# PT_2016_PB_MAIN_Rev1.net
KiCad netlist of a schematic drawn in EAGLE
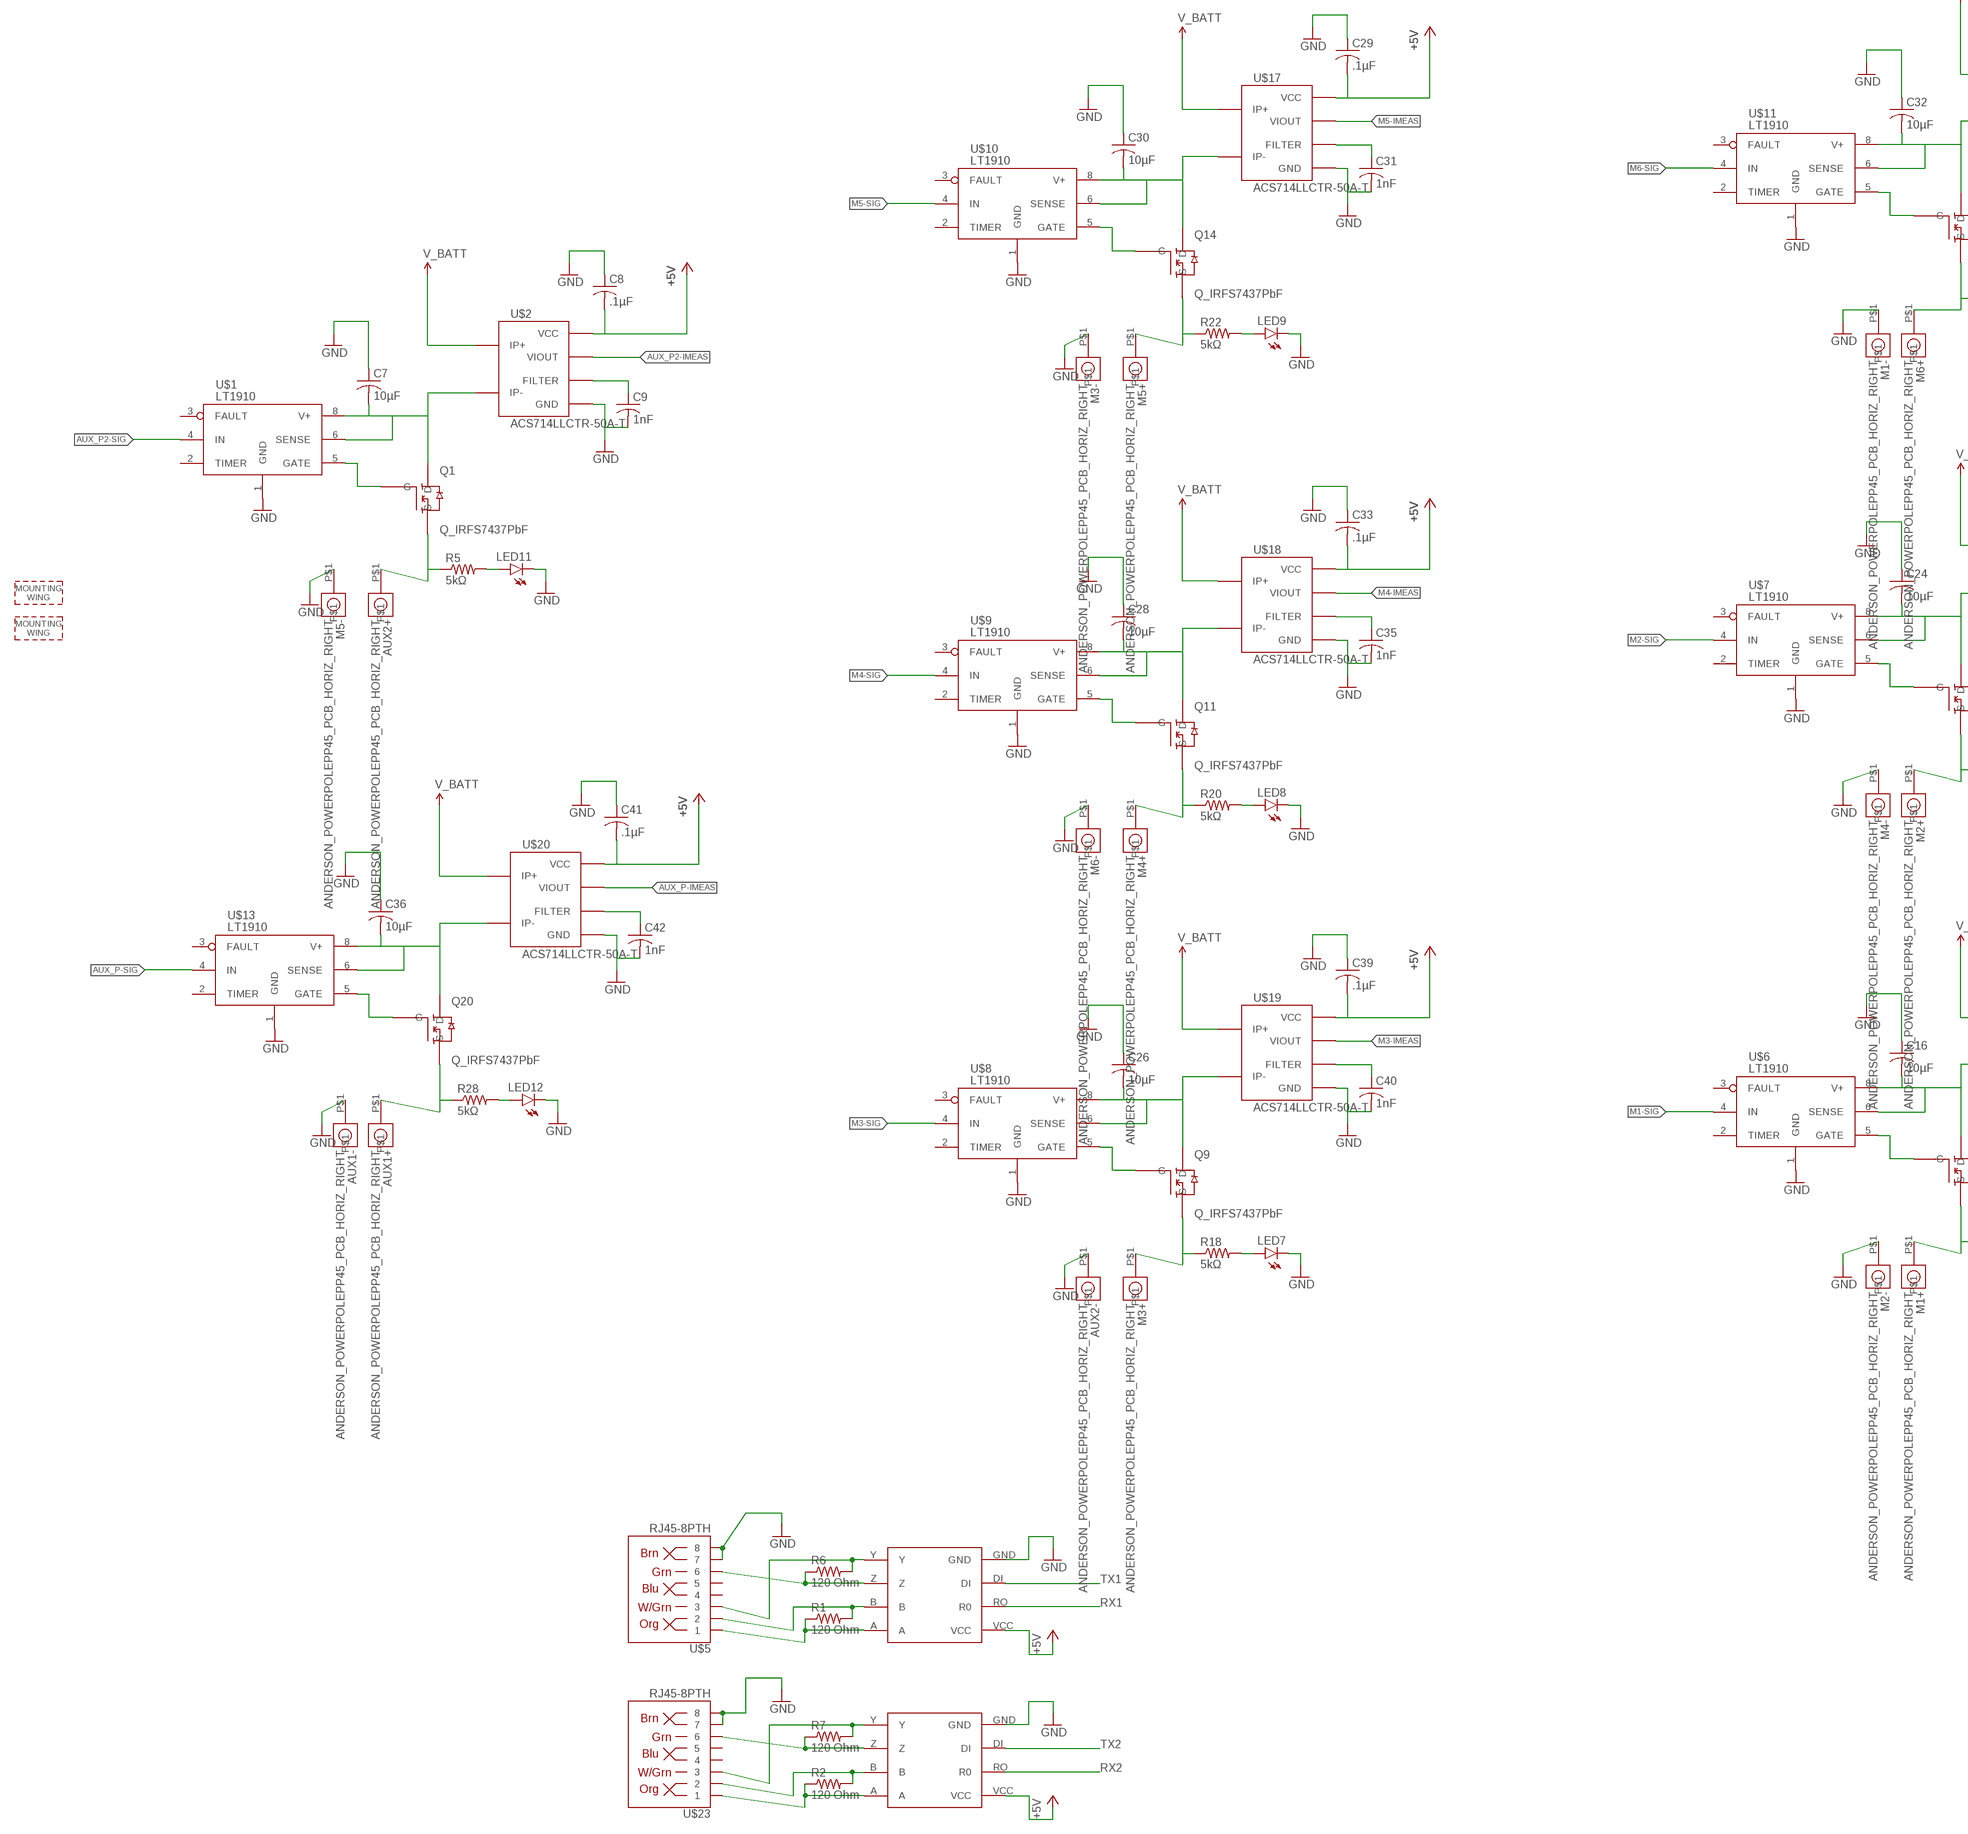
[diagram p0: schematic, sheet 1, part 1 of 2]
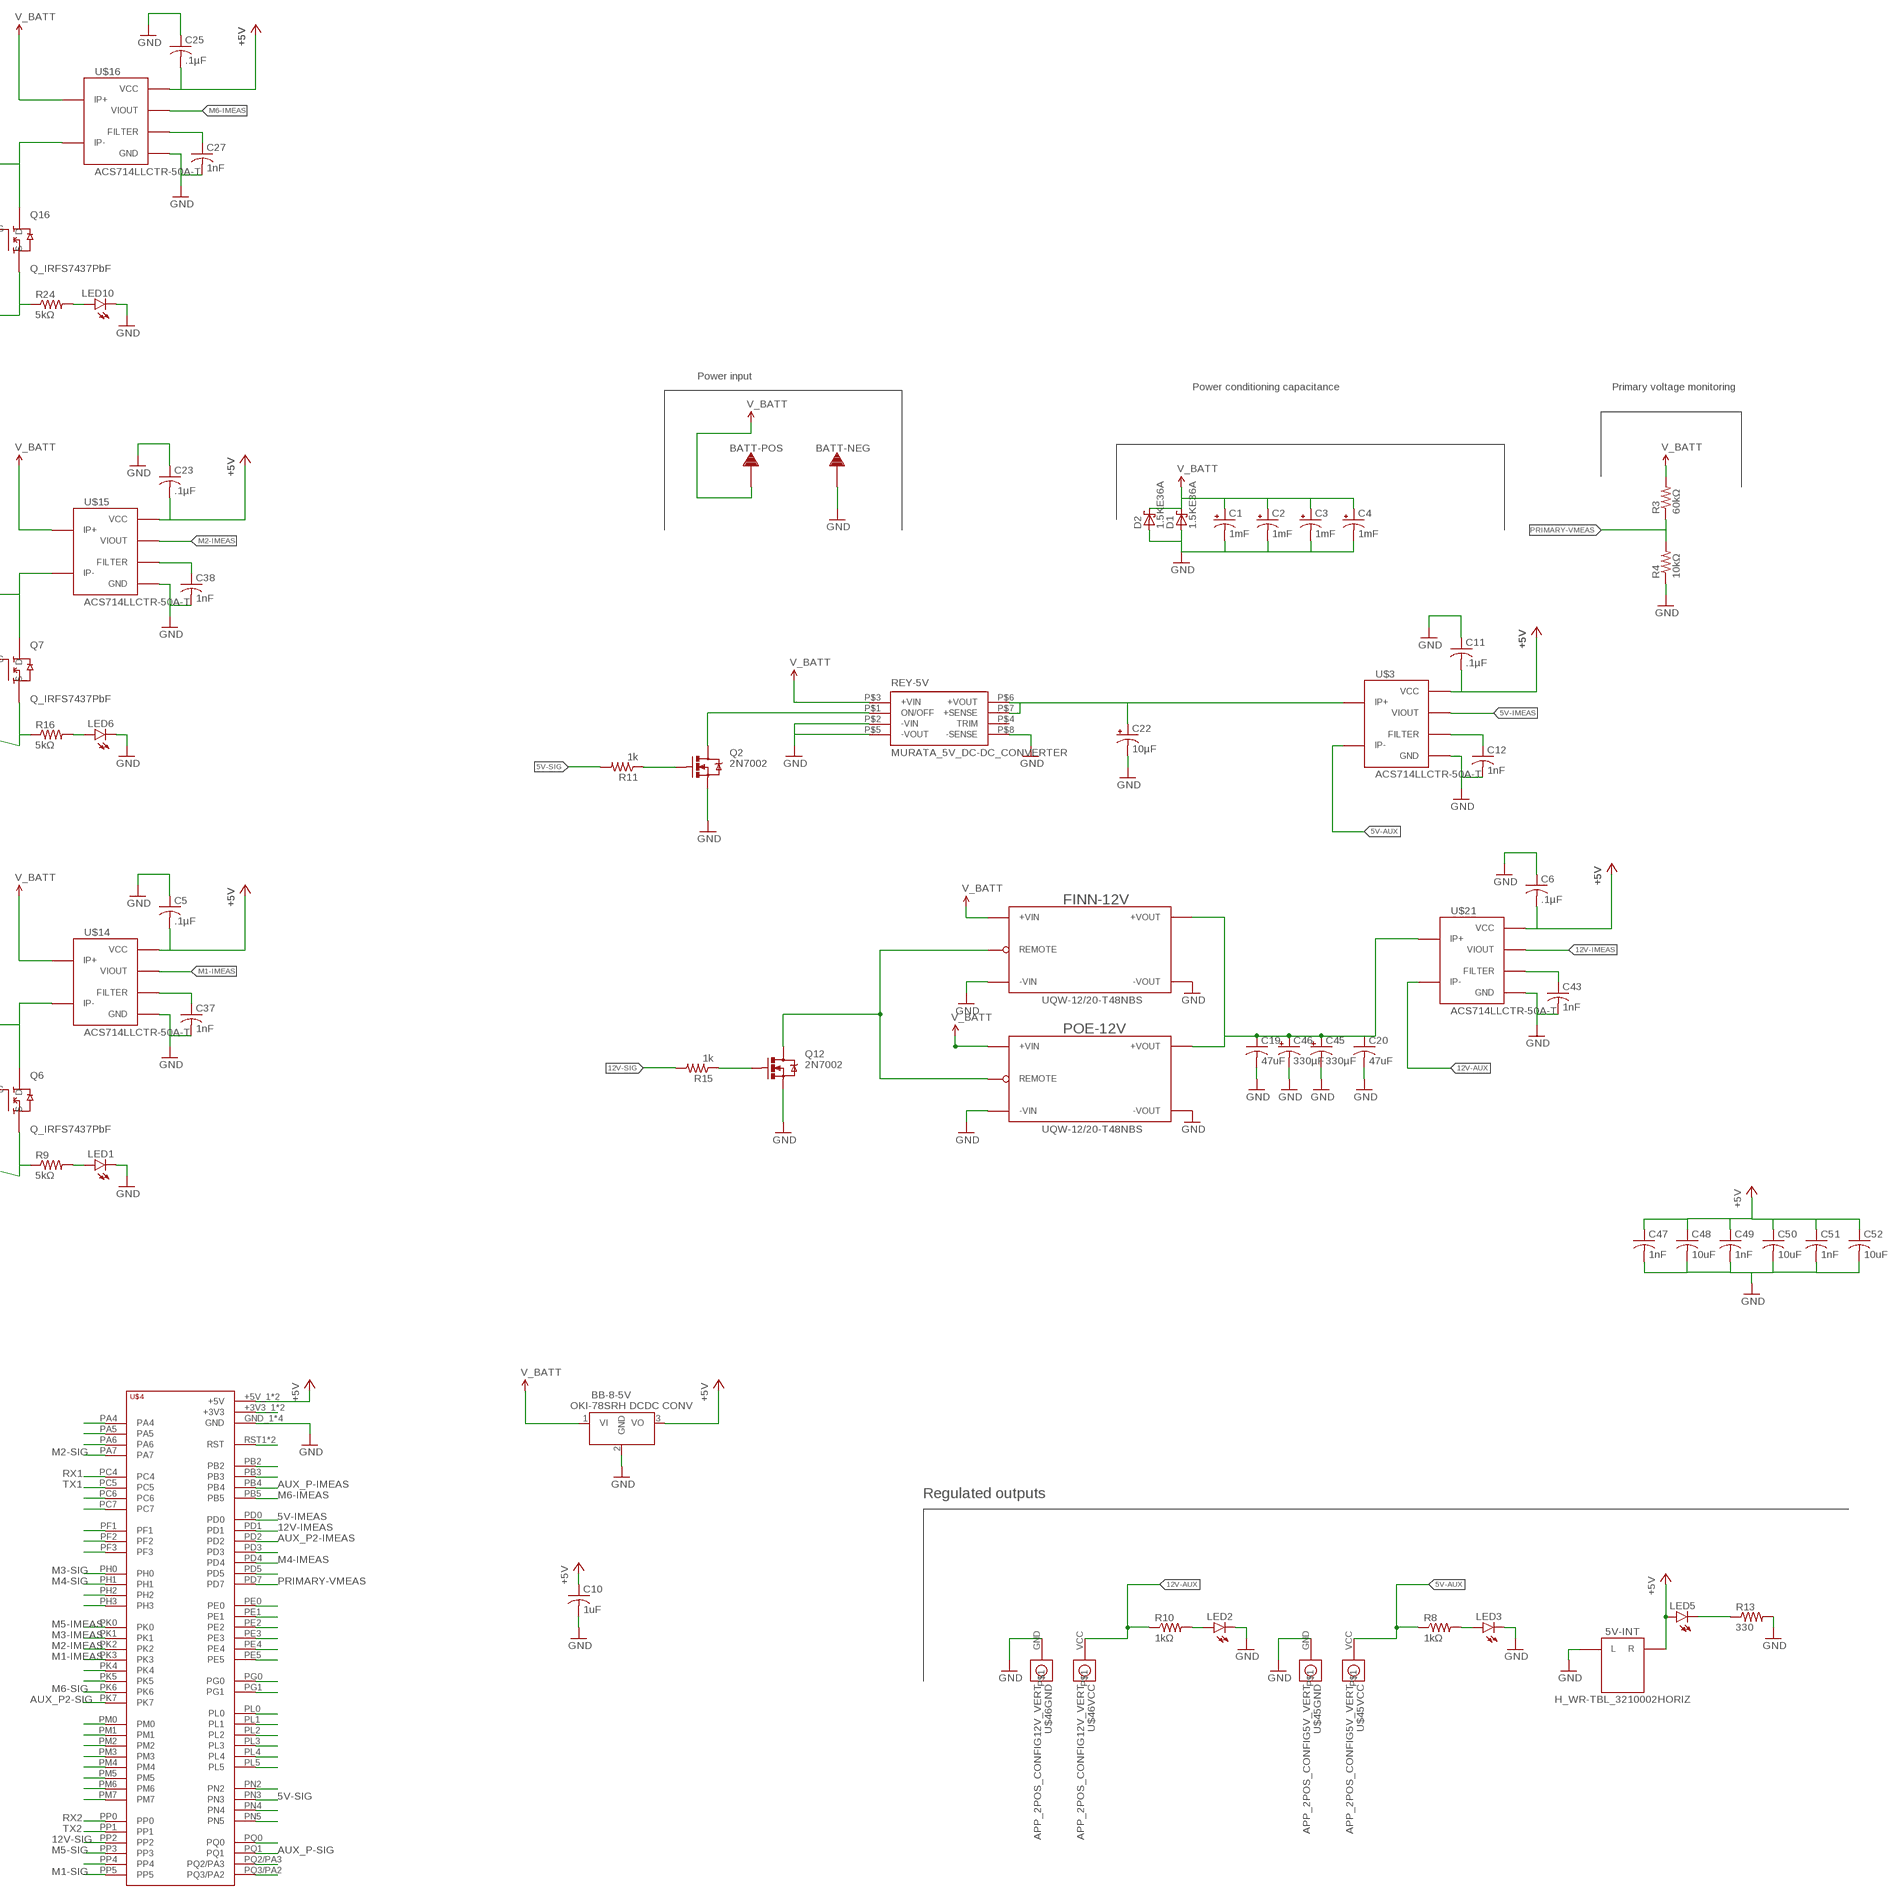
[diagram p1: schematic, sheet 1, part 2 of 2]

(export (version "E")
  (design (tool "Eeschema 10.0.6"))
  (components
    (comp (ref "5V-INT")
      (value "H_WR-TBL_3210002HORIZ")
      (footprint "eagle-import:691322110002")
      (libsource (lib "eagle-import") (part "H_WR-TBL_3210002HORIZ"))
    )
    (comp (ref "AUX1+")
      (value "ANDERSON_POWERPOLEPP45_PCB_HORIZ_RIGHT")
      (footprint "eagle-import:APP45_PCB_HORIZ_RIGHT")
      (libsource (lib "eagle-import") (part "ANDERSON_POWERPOLEPP45_PCB_HORIZ_RIGHT"))
    )
    (comp (ref "AUX1-")
      (value "ANDERSON_POWERPOLEPP45_PCB_HORIZ_RIGHT")
      (footprint "eagle-import:APP45_PCB_HORIZ_RIGHT")
      (libsource (lib "eagle-import") (part "ANDERSON_POWERPOLEPP45_PCB_HORIZ_RIGHT"))
    )
    (comp (ref "AUX2+")
      (value "ANDERSON_POWERPOLEPP45_PCB_HORIZ_RIGHT")
      (footprint "eagle-import:APP45_PCB_HORIZ_RIGHT")
      (libsource (lib "eagle-import") (part "ANDERSON_POWERPOLEPP45_PCB_HORIZ_RIGHT"))
    )
    (comp (ref "AUX2-")
      (value "ANDERSON_POWERPOLEPP45_PCB_HORIZ_RIGHT")
      (footprint "eagle-import:APP45_PCB_HORIZ_RIGHT")
      (libsource (lib "eagle-import") (part "ANDERSON_POWERPOLEPP45_PCB_HORIZ_RIGHT"))
    )
    (comp (ref "BATT-NEG")
      (value "TERMINAL_HOLE")
      (footprint "eagle-import:LARGE_TERMINAL_HOLE")
      (libsource (lib "eagle-import") (part "TERMINAL_HOLE"))
    )
    (comp (ref "BATT-POS")
      (value "TERMINAL_HOLE")
      (footprint "eagle-import:LARGE_TERMINAL_HOLE")
      (libsource (lib "eagle-import") (part "TERMINAL_HOLE"))
    )
    (comp (ref "BB-8-5V")
      (value "Q_OKI-78SR")
      (footprint "eagle-import:OKI-78SRH")
      (libsource (lib "eagle-import") (part "Q_OKI-78SR"))
    )
    (comp (ref "C1")
      (value "1mF")
      (footprint "eagle-import:C_12.5MM")
      (libsource (lib "eagle-import") (part "C_POL12.5MM_NORMAL"))
    )
    (comp (ref "C2")
      (value "1mF")
      (footprint "eagle-import:C_12.5MM")
      (libsource (lib "eagle-import") (part "C_POL12.5MM_NORMAL"))
    )
    (comp (ref "C3")
      (value "1mF")
      (footprint "eagle-import:C_12.5MM")
      (libsource (lib "eagle-import") (part "C_POL12.5MM_NORMAL"))
    )
    (comp (ref "C4")
      (value "1mF")
      (footprint "eagle-import:C_12.5MM")
      (libsource (lib "eagle-import") (part "C_POL12.5MM_NORMAL"))
    )
    (comp (ref "C5")
      (value ".1µF")
      (footprint "eagle-import:C1206")
      (libsource (lib "eagle-import") (part "C-USC1206"))
    )
    (comp (ref "C6")
      (value ".1µF")
      (footprint "eagle-import:C1206")
      (libsource (lib "eagle-import") (part "C-USC1206"))
    )
    (comp (ref "C7")
      (value "10µF")
      (footprint "eagle-import:C1206")
      (libsource (lib "eagle-import") (part "C-USC1206"))
    )
    (comp (ref "C8")
      (value ".1µF")
      (footprint "eagle-import:C1206")
      (libsource (lib "eagle-import") (part "C-USC1206"))
    )
    (comp (ref "C9")
      (value "1nF")
      (footprint "eagle-import:C1206")
      (libsource (lib "eagle-import") (part "C-USC1206"))
    )
    (comp (ref "C10")
      (value "1uF")
      (footprint "eagle-import:C1206")
      (libsource (lib "eagle-import") (part "C-USC1206"))
    )
    (comp (ref "C11")
      (value ".1µF")
      (footprint "eagle-import:C1206")
      (libsource (lib "eagle-import") (part "C-USC1206"))
    )
    (comp (ref "C12")
      (value "1nF")
      (footprint "eagle-import:C1206")
      (libsource (lib "eagle-import") (part "C-USC1206"))
    )
    (comp (ref "C16")
      (value "10µF")
      (footprint "eagle-import:C1206")
      (libsource (lib "eagle-import") (part "C-USC1206"))
    )
    (comp (ref "C19")
      (value "47uF")
      (footprint "eagle-import:C1206")
      (libsource (lib "eagle-import") (part "C-USC1206"))
    )
    (comp (ref "C20")
      (value "47uF")
      (footprint "eagle-import:C1206")
      (libsource (lib "eagle-import") (part "C-USC1206"))
    )
    (comp (ref "C22")
      (value "10µF")
      (footprint "eagle-import:E5-8,5")
      (libsource (lib "eagle-import") (part "CPOL-USE5-8.5"))
    )
    (comp (ref "C23")
      (value ".1µF")
      (footprint "eagle-import:C1206")
      (libsource (lib "eagle-import") (part "C-USC1206"))
    )
    (comp (ref "C24")
      (value "10µF")
      (footprint "eagle-import:C1206")
      (libsource (lib "eagle-import") (part "C-USC1206"))
    )
    (comp (ref "C25")
      (value ".1µF")
      (footprint "eagle-import:C1206")
      (libsource (lib "eagle-import") (part "C-USC1206"))
    )
    (comp (ref "C26")
      (value "10µF")
      (footprint "eagle-import:C1206")
      (libsource (lib "eagle-import") (part "C-USC1206"))
    )
    (comp (ref "C27")
      (value "1nF")
      (footprint "eagle-import:C1206")
      (libsource (lib "eagle-import") (part "C-USC1206"))
    )
    (comp (ref "C28")
      (value "10µF")
      (footprint "eagle-import:C1206")
      (libsource (lib "eagle-import") (part "C-USC1206"))
    )
    (comp (ref "C29")
      (value ".1µF")
      (footprint "eagle-import:C1206")
      (libsource (lib "eagle-import") (part "C-USC1206"))
    )
    (comp (ref "C30")
      (value "10µF")
      (footprint "eagle-import:C1206")
      (libsource (lib "eagle-import") (part "C-USC1206"))
    )
    (comp (ref "C31")
      (value "1nF")
      (footprint "eagle-import:C1206")
      (libsource (lib "eagle-import") (part "C-USC1206"))
    )
    (comp (ref "C32")
      (value "10µF")
      (footprint "eagle-import:C1206")
      (libsource (lib "eagle-import") (part "C-USC1206"))
    )
    (comp (ref "C33")
      (value ".1µF")
      (footprint "eagle-import:C1206")
      (libsource (lib "eagle-import") (part "C-USC1206"))
    )
    (comp (ref "C35")
      (value "1nF")
      (footprint "eagle-import:C1206")
      (libsource (lib "eagle-import") (part "C-USC1206"))
    )
    (comp (ref "C36")
      (value "10µF")
      (footprint "eagle-import:C1206")
      (libsource (lib "eagle-import") (part "C-USC1206"))
    )
    (comp (ref "C37")
      (value "1nF")
      (footprint "eagle-import:C1206")
      (libsource (lib "eagle-import") (part "C-USC1206"))
    )
    (comp (ref "C38")
      (value "1nF")
      (footprint "eagle-import:C1206")
      (libsource (lib "eagle-import") (part "C-USC1206"))
    )
    (comp (ref "C39")
      (value ".1µF")
      (footprint "eagle-import:C1206")
      (libsource (lib "eagle-import") (part "C-USC1206"))
    )
    (comp (ref "C40")
      (value "1nF")
      (footprint "eagle-import:C1206")
      (libsource (lib "eagle-import") (part "C-USC1206"))
    )
    (comp (ref "C41")
      (value ".1µF")
      (footprint "eagle-import:C1206")
      (libsource (lib "eagle-import") (part "C-USC1206"))
    )
    (comp (ref "C42")
      (value "1nF")
      (footprint "eagle-import:C1206")
      (libsource (lib "eagle-import") (part "C-USC1206"))
    )
    (comp (ref "C43")
      (value "1nF")
      (footprint "eagle-import:C1206")
      (libsource (lib "eagle-import") (part "C-USC1206"))
    )
    (comp (ref "C45")
      (value "330µF")
      (footprint "eagle-import:E5-8,5")
      (libsource (lib "eagle-import") (part "CPOL-USE5-8.5"))
    )
    (comp (ref "C46")
      (value "330µF")
      (footprint "eagle-import:E5-8,5")
      (libsource (lib "eagle-import") (part "CPOL-USE5-8.5"))
    )
    (comp (ref "C47")
      (value "1nF")
      (footprint "eagle-import:C1206")
      (libsource (lib "eagle-import") (part "C-USC1206"))
    )
    (comp (ref "C48")
      (value "10uF")
      (footprint "eagle-import:C1206")
      (libsource (lib "eagle-import") (part "C-USC1206"))
    )
    (comp (ref "C49")
      (value "1nF")
      (footprint "eagle-import:C1206")
      (libsource (lib "eagle-import") (part "C-USC1206"))
    )
    (comp (ref "C50")
      (value "10uF")
      (footprint "eagle-import:C1206")
      (libsource (lib "eagle-import") (part "C-USC1206"))
    )
    (comp (ref "C51")
      (value "1nF")
      (footprint "eagle-import:C1206")
      (libsource (lib "eagle-import") (part "C-USC1206"))
    )
    (comp (ref "C52")
      (value "10uF")
      (footprint "eagle-import:C1206")
      (libsource (lib "eagle-import") (part "C-USC1206"))
    )
    (comp (ref "D1")
      (value "1.5KE36A")
      (footprint "eagle-import:CB429-17")
      (libsource (lib "eagle-import") (part "15KEXX"))
    )
    (comp (ref "D2")
      (value "1.5KE36A")
      (footprint "eagle-import:CB429-17")
      (libsource (lib "eagle-import") (part "15KEXX"))
    )
    (comp (ref "FINN-12V")
      (value "UQW-12/20-T48NBS")
      (footprint "eagle-import:U-T48-QB-NO_TRIM")
      (libsource (lib "eagle-import") (part "UQW-12/20-T48NBS"))
    )
    (comp (ref "LED1")
      (value "LED1206")
      (footprint "eagle-import:LED-1206")
      (libsource (lib "eagle-import") (part "LED1206"))
    )
    (comp (ref "LED2")
      (value "LED1206")
      (footprint "eagle-import:LED-1206")
      (libsource (lib "eagle-import") (part "LED1206"))
    )
    (comp (ref "LED3")
      (value "LED1206")
      (footprint "eagle-import:LED-1206")
      (libsource (lib "eagle-import") (part "LED1206"))
    )
    (comp (ref "LED5")
      (value "LED1206")
      (footprint "eagle-import:LED-1206")
      (libsource (lib "eagle-import") (part "LED1206"))
    )
    (comp (ref "LED6")
      (value "LED1206")
      (footprint "eagle-import:LED-1206")
      (libsource (lib "eagle-import") (part "LED1206"))
    )
    (comp (ref "LED7")
      (value "LED1206")
      (footprint "eagle-import:LED-1206")
      (libsource (lib "eagle-import") (part "LED1206"))
    )
    (comp (ref "LED8")
      (value "LED1206")
      (footprint "eagle-import:LED-1206")
      (libsource (lib "eagle-import") (part "LED1206"))
    )
    (comp (ref "LED9")
      (value "LED1206")
      (footprint "eagle-import:LED-1206")
      (libsource (lib "eagle-import") (part "LED1206"))
    )
    (comp (ref "LED10")
      (value "LED1206")
      (footprint "eagle-import:LED-1206")
      (libsource (lib "eagle-import") (part "LED1206"))
    )
    (comp (ref "LED11")
      (value "LED1206")
      (footprint "eagle-import:LED-1206")
      (libsource (lib "eagle-import") (part "LED1206"))
    )
    (comp (ref "LED12")
      (value "LED1206")
      (footprint "eagle-import:LED-1206")
      (libsource (lib "eagle-import") (part "LED1206"))
    )
    (comp (ref "M1+")
      (value "ANDERSON_POWERPOLEPP45_PCB_HORIZ_RIGHT")
      (footprint "eagle-import:APP45_PCB_HORIZ_RIGHT")
      (libsource (lib "eagle-import") (part "ANDERSON_POWERPOLEPP45_PCB_HORIZ_RIGHT"))
    )
    (comp (ref "M1-")
      (value "ANDERSON_POWERPOLEPP45_PCB_HORIZ_RIGHT")
      (footprint "eagle-import:APP45_PCB_HORIZ_RIGHT")
      (libsource (lib "eagle-import") (part "ANDERSON_POWERPOLEPP45_PCB_HORIZ_RIGHT"))
    )
    (comp (ref "M2+")
      (value "ANDERSON_POWERPOLEPP45_PCB_HORIZ_RIGHT")
      (footprint "eagle-import:APP45_PCB_HORIZ_RIGHT")
      (libsource (lib "eagle-import") (part "ANDERSON_POWERPOLEPP45_PCB_HORIZ_RIGHT"))
    )
    (comp (ref "M2-")
      (value "ANDERSON_POWERPOLEPP45_PCB_HORIZ_RIGHT")
      (footprint "eagle-import:APP45_PCB_HORIZ_RIGHT")
      (libsource (lib "eagle-import") (part "ANDERSON_POWERPOLEPP45_PCB_HORIZ_RIGHT"))
    )
    (comp (ref "M3+")
      (value "ANDERSON_POWERPOLEPP45_PCB_HORIZ_RIGHT")
      (footprint "eagle-import:APP45_PCB_HORIZ_RIGHT")
      (libsource (lib "eagle-import") (part "ANDERSON_POWERPOLEPP45_PCB_HORIZ_RIGHT"))
    )
    (comp (ref "M3-")
      (value "ANDERSON_POWERPOLEPP45_PCB_HORIZ_RIGHT")
      (footprint "eagle-import:APP45_PCB_HORIZ_RIGHT")
      (libsource (lib "eagle-import") (part "ANDERSON_POWERPOLEPP45_PCB_HORIZ_RIGHT"))
    )
    (comp (ref "M4+")
      (value "ANDERSON_POWERPOLEPP45_PCB_HORIZ_RIGHT")
      (footprint "eagle-import:APP45_PCB_HORIZ_RIGHT")
      (libsource (lib "eagle-import") (part "ANDERSON_POWERPOLEPP45_PCB_HORIZ_RIGHT"))
    )
    (comp (ref "M4-")
      (value "ANDERSON_POWERPOLEPP45_PCB_HORIZ_RIGHT")
      (footprint "eagle-import:APP45_PCB_HORIZ_RIGHT")
      (libsource (lib "eagle-import") (part "ANDERSON_POWERPOLEPP45_PCB_HORIZ_RIGHT"))
    )
    (comp (ref "M5+")
      (value "ANDERSON_POWERPOLEPP45_PCB_HORIZ_RIGHT")
      (footprint "eagle-import:APP45_PCB_HORIZ_RIGHT")
      (libsource (lib "eagle-import") (part "ANDERSON_POWERPOLEPP45_PCB_HORIZ_RIGHT"))
    )
    (comp (ref "M5-")
      (value "ANDERSON_POWERPOLEPP45_PCB_HORIZ_RIGHT")
      (footprint "eagle-import:APP45_PCB_HORIZ_RIGHT")
      (libsource (lib "eagle-import") (part "ANDERSON_POWERPOLEPP45_PCB_HORIZ_RIGHT"))
    )
    (comp (ref "M6+")
      (value "ANDERSON_POWERPOLEPP45_PCB_HORIZ_RIGHT")
      (footprint "eagle-import:APP45_PCB_HORIZ_RIGHT")
      (libsource (lib "eagle-import") (part "ANDERSON_POWERPOLEPP45_PCB_HORIZ_RIGHT"))
    )
    (comp (ref "M6-")
      (value "ANDERSON_POWERPOLEPP45_PCB_HORIZ_RIGHT")
      (footprint "eagle-import:APP45_PCB_HORIZ_RIGHT")
      (libsource (lib "eagle-import") (part "ANDERSON_POWERPOLEPP45_PCB_HORIZ_RIGHT"))
    )
    (comp (ref "POE-12V")
      (value "UQW-12/20-T48NBS")
      (footprint "eagle-import:U-T48-QB-NO_TRIM")
      (libsource (lib "eagle-import") (part "UQW-12/20-T48NBS"))
    )
    (comp (ref "Q1")
      (value "Q_IRFS7437PbF")
      (footprint "eagle-import:D2PACK")
      (libsource (lib "eagle-import") (part "Q_IRF7437SMD"))
    )
    (comp (ref "Q2")
      (value "2N7002")
      (footprint "eagle-import:SOT323")
      (libsource (lib "eagle-import") (part "MOSFET-NCHANNEL2N7002PW"))
    )
    (comp (ref "Q6")
      (value "Q_IRFS7437PbF")
      (footprint "eagle-import:D2PACK")
      (libsource (lib "eagle-import") (part "Q_IRF7437SMD"))
    )
    (comp (ref "Q7")
      (value "Q_IRFS7437PbF")
      (footprint "eagle-import:D2PACK")
      (libsource (lib "eagle-import") (part "Q_IRF7437SMD"))
    )
    (comp (ref "Q9")
      (value "Q_IRFS7437PbF")
      (footprint "eagle-import:D2PACK")
      (libsource (lib "eagle-import") (part "Q_IRF7437SMD"))
    )
    (comp (ref "Q11")
      (value "Q_IRFS7437PbF")
      (footprint "eagle-import:D2PACK")
      (libsource (lib "eagle-import") (part "Q_IRF7437SMD"))
    )
    (comp (ref "Q12")
      (value "2N7002")
      (footprint "eagle-import:SOT323")
      (libsource (lib "eagle-import") (part "MOSFET-NCHANNEL2N7002PW"))
    )
    (comp (ref "Q14")
      (value "Q_IRFS7437PbF")
      (footprint "eagle-import:D2PACK")
      (libsource (lib "eagle-import") (part "Q_IRF7437SMD"))
    )
    (comp (ref "Q16")
      (value "Q_IRFS7437PbF")
      (footprint "eagle-import:D2PACK")
      (libsource (lib "eagle-import") (part "Q_IRF7437SMD"))
    )
    (comp (ref "Q20")
      (value "Q_IRFS7437PbF")
      (footprint "eagle-import:D2PACK")
      (libsource (lib "eagle-import") (part "Q_IRF7437SMD"))
    )
    (comp (ref "R1")
      (value "120 Ohm")
      (footprint "eagle-import:1206")
      (libsource (lib "eagle-import") (part "RESISTOR1206"))
    )
    (comp (ref "R2")
      (value "120 Ohm")
      (footprint "eagle-import:1206")
      (libsource (lib "eagle-import") (part "RESISTOR1206"))
    )
    (comp (ref "R3")
      (value "60kΩ")
      (footprint "eagle-import:R1206")
      (libsource (lib "eagle-import") (part "R-US_R1206"))
    )
    (comp (ref "R4")
      (value "10kΩ")
      (footprint "eagle-import:R1206")
      (libsource (lib "eagle-import") (part "R-US_R1206"))
    )
    (comp (ref "R5")
      (value "5kΩ")
      (footprint "eagle-import:1206")
      (libsource (lib "eagle-import") (part "RESISTOR1206"))
    )
    (comp (ref "R6")
      (value "120 Ohm")
      (footprint "eagle-import:1206")
      (libsource (lib "eagle-import") (part "RESISTOR1206"))
    )
    (comp (ref "R7")
      (value "120 Ohm")
      (footprint "eagle-import:1206")
      (libsource (lib "eagle-import") (part "RESISTOR1206"))
    )
    (comp (ref "R8")
      (value "1kΩ")
      (footprint "eagle-import:1206")
      (libsource (lib "eagle-import") (part "RESISTOR1206"))
    )
    (comp (ref "R9")
      (value "5kΩ")
      (footprint "eagle-import:1206")
      (libsource (lib "eagle-import") (part "RESISTOR1206"))
    )
    (comp (ref "R10")
      (value "1kΩ")
      (footprint "eagle-import:1206")
      (libsource (lib "eagle-import") (part "RESISTOR1206"))
    )
    (comp (ref "R11")
      (value "1k")
      (footprint "eagle-import:R1206")
      (libsource (lib "eagle-import") (part "R-US_R1206"))
    )
    (comp (ref "R13")
      (value "330")
      (footprint "eagle-import:1206")
      (libsource (lib "eagle-import") (part "RESISTOR1206"))
    )
    (comp (ref "R15")
      (value "1k")
      (footprint "eagle-import:R1206")
      (libsource (lib "eagle-import") (part "R-US_R1206"))
    )
    (comp (ref "R16")
      (value "5kΩ")
      (footprint "eagle-import:1206")
      (libsource (lib "eagle-import") (part "RESISTOR1206"))
    )
    (comp (ref "R18")
      (value "5kΩ")
      (footprint "eagle-import:1206")
      (libsource (lib "eagle-import") (part "RESISTOR1206"))
    )
    (comp (ref "R20")
      (value "5kΩ")
      (footprint "eagle-import:1206")
      (libsource (lib "eagle-import") (part "RESISTOR1206"))
    )
    (comp (ref "R22")
      (value "5kΩ")
      (footprint "eagle-import:1206")
      (libsource (lib "eagle-import") (part "RESISTOR1206"))
    )
    (comp (ref "R24")
      (value "5kΩ")
      (footprint "eagle-import:1206")
      (libsource (lib "eagle-import") (part "RESISTOR1206"))
    )
    (comp (ref "R28")
      (value "5kΩ")
      (footprint "eagle-import:1206")
      (libsource (lib "eagle-import") (part "RESISTOR1206"))
    )
    (comp (ref "REY-5V")
      (value "MURATA_5V_DC-DC_CONVERTER")
      (footprint "eagle-import:MURATA_5V_DC-DC_CONVERTER")
      (libsource (lib "eagle-import") (part "MURATA_5V_DC-DC_CONVERTER"))
    )
    (comp (ref "U$1")
      (value "LT1910")
      (footprint "eagle-import:SO8")
      (libsource (lib "eagle-import") (part "LT1910"))
    )
    (comp (ref "U$2")
      (value "ACS714LLCTR-50A-T")
      (footprint "eagle-import:SOIC8_ACS711_SKETCH")
      (libsource (lib "eagle-import") (part "Q_ACS714_SKETCH"))
    )
    (comp (ref "U$3")
      (value "ACS714LLCTR-50A-T")
      (footprint "eagle-import:SOIC8_ACS711")
      (libsource (lib "eagle-import") (part "Q_ACS714"))
    )
    (comp (ref "U$4")
      (value "TIVA-C-CONNECTED")
      (footprint "eagle-import:TIVA-C-CONNECTED")
      (libsource (lib "eagle-import") (part "TIVA-C-CONNECTED"))
    )
    (comp (ref "U$5")
      (value "RJ45-8PTH")
      (footprint "eagle-import:RJ45-8")
      (libsource (lib "eagle-import") (part "RJ45-8PTH"))
    )
    (comp (ref "U$6")
      (value "LT1910")
      (footprint "eagle-import:SO8")
      (libsource (lib "eagle-import") (part "LT1910"))
    )
    (comp (ref "U$7")
      (value "LT1910")
      (footprint "eagle-import:SO8")
      (libsource (lib "eagle-import") (part "LT1910"))
    )
    (comp (ref "U$8")
      (value "LT1910")
      (footprint "eagle-import:SO8")
      (libsource (lib "eagle-import") (part "LT1910"))
    )
    (comp (ref "U$9")
      (value "LT1910")
      (footprint "eagle-import:SO8")
      (libsource (lib "eagle-import") (part "LT1910"))
    )
    (comp (ref "U$10")
      (value "LT1910")
      (footprint "eagle-import:SO8")
      (libsource (lib "eagle-import") (part "LT1910"))
    )
    (comp (ref "U$11")
      (value "LT1910")
      (footprint "eagle-import:SO8")
      (libsource (lib "eagle-import") (part "LT1910"))
    )
    (comp (ref "U$12")
      (value "MAX3077")
      (footprint "eagle-import:MAX3070E")
      (libsource (lib "eagle-import") (part "MAX3077"))
    )
    (comp (ref "U$13")
      (value "LT1910")
      (footprint "eagle-import:SO8")
      (libsource (lib "eagle-import") (part "LT1910"))
    )
    (comp (ref "U$14")
      (value "ACS714LLCTR-50A-T")
      (footprint "eagle-import:SOIC8_ACS711_SKETCH")
      (libsource (lib "eagle-import") (part "Q_ACS714_SKETCH"))
    )
    (comp (ref "U$15")
      (value "ACS714LLCTR-50A-T")
      (footprint "eagle-import:SOIC8_ACS711_SKETCH")
      (libsource (lib "eagle-import") (part "Q_ACS714_SKETCH"))
    )
    (comp (ref "U$16")
      (value "ACS714LLCTR-50A-T")
      (footprint "eagle-import:SOIC8_ACS711_SKETCH")
      (libsource (lib "eagle-import") (part "Q_ACS714_SKETCH"))
    )
    (comp (ref "U$17")
      (value "ACS714LLCTR-50A-T")
      (footprint "eagle-import:SOIC8_ACS711_SKETCH")
      (libsource (lib "eagle-import") (part "Q_ACS714_SKETCH"))
    )
    (comp (ref "U$18")
      (value "ACS714LLCTR-50A-T")
      (footprint "eagle-import:SOIC8_ACS711_SKETCH")
      (libsource (lib "eagle-import") (part "Q_ACS714_SKETCH"))
    )
    (comp (ref "U$19")
      (value "ACS714LLCTR-50A-T")
      (footprint "eagle-import:SOIC8_ACS711_SKETCH")
      (libsource (lib "eagle-import") (part "Q_ACS714_SKETCH"))
    )
    (comp (ref "U$20")
      (value "ACS714LLCTR-50A-T")
      (footprint "eagle-import:SOIC8_ACS711_SKETCH")
      (libsource (lib "eagle-import") (part "Q_ACS714_SKETCH"))
    )
    (comp (ref "U$21")
      (value "ACS714LLCTR-50A-T")
      (footprint "eagle-import:SOIC8_ACS711")
      (libsource (lib "eagle-import") (part "Q_ACS714"))
    )
    (comp (ref "U$23")
      (value "RJ45-8PTH")
      (footprint "eagle-import:RJ45-8")
      (libsource (lib "eagle-import") (part "RJ45-8PTH"))
    )
    (comp (ref "U$24")
      (value "MAX3077")
      (footprint "eagle-import:MAX3070E")
      (libsource (lib "eagle-import") (part "MAX3077"))
    )
    (comp (ref "U$41")
      (value "APP_MOUTING_WINGHORIZ")
      (footprint "eagle-import:APP45_MOUNTING_WING_HORIZ")
      (libsource (lib "eagle-import") (part "APP_MOUTING_WINGHORIZ"))
    )
    (comp (ref "U$42")
      (value "APP_MOUTING_WINGHORIZ")
      (footprint "eagle-import:APP45_MOUNTING_WING_HORIZ")
      (libsource (lib "eagle-import") (part "APP_MOUTING_WINGHORIZ"))
    )
    (comp (ref "U$45")
      (value "APP_2POS_CONFIG5V_VERT")
      (footprint "eagle-import:APP45_5V_VERT_CONFIG")
      (libsource (lib "eagle-import") (part "APP_2POS_CONFIG5V_VERT"))
    )
    (comp (ref "U$46")
      (value "APP_2POS_CONFIG12V_VERT")
      (footprint "eagle-import:APP45_12V_VERT_CONFIG")
      (libsource (lib "eagle-import") (part "APP_2POS_CONFIG12V_VERT"))
    )
  )
  (nets
    (net (code "1") (name "+5V") (class "Default")
      (node (ref "5V-INT") (pin "R") (pinfunction "R_R") (pintype "bidirectional"))
      (node (ref "BB-8-5V") (pin "3") (pinfunction "VO_3") (pintype "bidirectional"))
      (node (ref "C10") (pin "1") (pinfunction "1_1") (pintype "passive"))
      (node (ref "C11") (pin "2") (pinfunction "2_2") (pintype "passive"))
      (node (ref "C23") (pin "2") (pinfunction "2_2") (pintype "passive"))
      (node (ref "C25") (pin "2") (pinfunction "2_2") (pintype "passive"))
      (node (ref "C29") (pin "2") (pinfunction "2_2") (pintype "passive"))
      (node (ref "C33") (pin "2") (pinfunction "2_2") (pintype "passive"))
      (node (ref "C39") (pin "2") (pinfunction "2_2") (pintype "passive"))
      (node (ref "C41") (pin "2") (pinfunction "2_2") (pintype "passive"))
      (node (ref "C47") (pin "1") (pinfunction "1_1") (pintype "passive"))
      (node (ref "C48") (pin "1") (pinfunction "1_1") (pintype "passive"))
      (node (ref "C49") (pin "1") (pinfunction "1_1") (pintype "passive"))
      (node (ref "C5") (pin "2") (pinfunction "2_2") (pintype "passive"))
      (node (ref "C50") (pin "1") (pinfunction "1_1") (pintype "passive"))
      (node (ref "C51") (pin "1") (pinfunction "1_1") (pintype "passive"))
      (node (ref "C52") (pin "1") (pinfunction "1_1") (pintype "passive"))
      (node (ref "C6") (pin "2") (pinfunction "2_2") (pintype "passive"))
      (node (ref "C8") (pin "2") (pinfunction "2_2") (pintype "passive"))
      (node (ref "LED5") (pin "A") (pinfunction "A_A") (pintype "passive"))
      (node (ref "U$12") (pin "VCC") (pinfunction "VCC_VCC") (pintype "bidirectional"))
      (node (ref "U$14") (pin "8") (pinfunction "VCC_8") (pintype "bidirectional"))
      (node (ref "U$15") (pin "8") (pinfunction "VCC_8") (pintype "bidirectional"))
      (node (ref "U$16") (pin "8") (pinfunction "VCC_8") (pintype "bidirectional"))
      (node (ref "U$17") (pin "8") (pinfunction "VCC_8") (pintype "bidirectional"))
      (node (ref "U$18") (pin "8") (pinfunction "VCC_8") (pintype "bidirectional"))
      (node (ref "U$19") (pin "8") (pinfunction "VCC_8") (pintype "bidirectional"))
      (node (ref "U$2") (pin "8") (pinfunction "VCC_8") (pintype "bidirectional"))
      (node (ref "U$20") (pin "8") (pinfunction "VCC_8") (pintype "bidirectional"))
      (node (ref "U$21") (pin "8") (pinfunction "VCC_8") (pintype "bidirectional"))
      (node (ref "U$24") (pin "VCC") (pinfunction "VCC_VCC") (pintype "bidirectional"))
      (node (ref "U$3") (pin "8") (pinfunction "VCC_8") (pintype "bidirectional"))
      (node (ref "U$4") (pin "+5V_1") (pinfunction "+5V_+5V_1") (pintype "bidirectional"))
      (node (ref "U$4") (pin "+5V_2") (pinfunction "+5V_+5V_2") (pintype "bidirectional"))
    )
    (net (code "2") (name "/RX1") (class "Default")
      (node (ref "U$12") (pin "RO") (pinfunction "R0_RO") (pintype "bidirectional"))
      (node (ref "U$4") (pin "PC4") (pinfunction "PC4_PC4") (pintype "bidirectional"))
    )
    (net (code "3") (name "/RX2") (class "Default")
      (node (ref "U$24") (pin "RO") (pinfunction "R0_RO") (pintype "bidirectional"))
      (node (ref "U$4") (pin "PP0") (pinfunction "PP0_PP0") (pintype "bidirectional"))
    )
    (net (code "4") (name "/TX1") (class "Default")
      (node (ref "U$12") (pin "DI") (pinfunction "DI_DI") (pintype "bidirectional"))
      (node (ref "U$4") (pin "PC5") (pinfunction "PC5_PC5") (pintype "bidirectional"))
    )
    (net (code "5") (name "/TX2") (class "Default")
      (node (ref "U$24") (pin "DI") (pinfunction "DI_DI") (pintype "bidirectional"))
      (node (ref "U$4") (pin "PP1") (pinfunction "PP1_PP1") (pintype "bidirectional"))
    )
    (net (code "6") (name "5V-AUX") (class "Default")
      (node (ref "R8") (pin "1") (pinfunction "1_1") (pintype "passive"))
      (node (ref "U$3") (pin "4") (pinfunction "IP-_4") (pintype "bidirectional"))
      (node (ref "U$45") (pin "VCC") (pinfunction "P$1_VCC") (pintype "bidirectional"))
    )
    (net (code "7") (name "5V-IMEAS") (class "Default")
      (node (ref "U$3") (pin "7") (pinfunction "VIOUT_7") (pintype "bidirectional"))
      (node (ref "U$4") (pin "PD0") (pinfunction "PD0_PD0") (pintype "bidirectional"))
    )
    (net (code "8") (name "5V-SIG") (class "Default")
      (node (ref "R11") (pin "2") (pinfunction "2_2") (pintype "passive"))
      (node (ref "U$4") (pin "PN3") (pinfunction "PN3_PN3") (pintype "bidirectional"))
    )
    (net (code "9") (name "12V-AUX") (class "Default")
      (node (ref "R10") (pin "1") (pinfunction "1_1") (pintype "passive"))
      (node (ref "U$21") (pin "4") (pinfunction "IP-_4") (pintype "bidirectional"))
      (node (ref "U$46") (pin "VCC") (pinfunction "P$1_VCC") (pintype "bidirectional"))
    )
    (net (code "10") (name "12V-IMEAS") (class "Default")
      (node (ref "U$21") (pin "7") (pinfunction "VIOUT_7") (pintype "bidirectional"))
      (node (ref "U$4") (pin "PD1") (pinfunction "PD1_PD1") (pintype "bidirectional"))
    )
    (net (code "11") (name "12V-SIG") (class "Default")
      (node (ref "R15") (pin "2") (pinfunction "2_2") (pintype "passive"))
      (node (ref "U$4") (pin "PP2") (pinfunction "PP2_PP2") (pintype "bidirectional"))
    )
    (net (code "12") (name "AUX_P-IMEAS") (class "Default")
      (node (ref "U$20") (pin "7") (pinfunction "VIOUT_7") (pintype "bidirectional"))
      (node (ref "U$4") (pin "PB4") (pinfunction "PB4_PB4") (pintype "bidirectional"))
    )
    (net (code "13") (name "AUX_P-SIG") (class "Default")
      (node (ref "U$13") (pin "4") (pinfunction "IN_4") (pintype "bidirectional"))
      (node (ref "U$4") (pin "PQ1") (pinfunction "PQ1_PQ1") (pintype "bidirectional"))
    )
    (net (code "14") (name "AUX_P2-IMEAS") (class "Default")
      (node (ref "U$2") (pin "7") (pinfunction "VIOUT_7") (pintype "bidirectional"))
      (node (ref "U$4") (pin "PD2") (pinfunction "PD2_PD2") (pintype "bidirectional"))
    )
    (net (code "15") (name "AUX_P2-SIG") (class "Default")
      (node (ref "U$1") (pin "4") (pinfunction "IN_4") (pintype "bidirectional"))
      (node (ref "U$4") (pin "PK7") (pinfunction "PK7_PK7") (pintype "bidirectional"))
    )
    (net (code "16") (name "GND") (class "Default")
      (node (ref "5V-INT") (pin "L") (pinfunction "L_L") (pintype "bidirectional"))
      (node (ref "AUX1-") (pin "P$1") (pinfunction "P$1_P$1") (pintype "bidirectional"))
      (node (ref "AUX2-") (pin "P$1") (pinfunction "P$1_P$1") (pintype "bidirectional"))
      (node (ref "BATT-NEG") (pin "P$1") (pinfunction "P$1_P$1") (pintype "bidirectional"))
      (node (ref "BB-8-5V") (pin "2") (pinfunction "GND_2") (pintype "bidirectional"))
      (node (ref "C1") (pin "-") (pinfunction "-_-") (pintype "passive"))
      (node (ref "C10") (pin "2") (pinfunction "2_2") (pintype "passive"))
      (node (ref "C11") (pin "1") (pinfunction "1_1") (pintype "passive"))
      (node (ref "C12") (pin "2") (pinfunction "2_2") (pintype "passive"))
      (node (ref "C16") (pin "1") (pinfunction "1_1") (pintype "passive"))
      (node (ref "C19") (pin "2") (pinfunction "2_2") (pintype "passive"))
      (node (ref "C2") (pin "-") (pinfunction "-_-") (pintype "passive"))
      (node (ref "C20") (pin "2") (pinfunction "2_2") (pintype "passive"))
      (node (ref "C22") (pin "-") (pinfunction "-_-") (pintype "passive"))
      (node (ref "C23") (pin "1") (pinfunction "1_1") (pintype "passive"))
      (node (ref "C24") (pin "1") (pinfunction "1_1") (pintype "passive"))
      (node (ref "C25") (pin "1") (pinfunction "1_1") (pintype "passive"))
      (node (ref "C26") (pin "1") (pinfunction "1_1") (pintype "passive"))
      (node (ref "C27") (pin "2") (pinfunction "2_2") (pintype "passive"))
      (node (ref "C28") (pin "1") (pinfunction "1_1") (pintype "passive"))
      (node (ref "C29") (pin "1") (pinfunction "1_1") (pintype "passive"))
      (node (ref "C3") (pin "-") (pinfunction "-_-") (pintype "passive"))
      (node (ref "C30") (pin "1") (pinfunction "1_1") (pintype "passive"))
      (node (ref "C31") (pin "2") (pinfunction "2_2") (pintype "passive"))
      (node (ref "C32") (pin "1") (pinfunction "1_1") (pintype "passive"))
      (node (ref "C33") (pin "1") (pinfunction "1_1") (pintype "passive"))
      (node (ref "C35") (pin "2") (pinfunction "2_2") (pintype "passive"))
      (node (ref "C36") (pin "1") (pinfunction "1_1") (pintype "passive"))
      (node (ref "C37") (pin "2") (pinfunction "2_2") (pintype "passive"))
      (node (ref "C38") (pin "2") (pinfunction "2_2") (pintype "passive"))
      (node (ref "C39") (pin "1") (pinfunction "1_1") (pintype "passive"))
      (node (ref "C4") (pin "-") (pinfunction "-_-") (pintype "passive"))
      (node (ref "C40") (pin "2") (pinfunction "2_2") (pintype "passive"))
      (node (ref "C41") (pin "1") (pinfunction "1_1") (pintype "passive"))
      (node (ref "C42") (pin "2") (pinfunction "2_2") (pintype "passive"))
      (node (ref "C43") (pin "2") (pinfunction "2_2") (pintype "passive"))
      (node (ref "C45") (pin "-") (pinfunction "-_-") (pintype "passive"))
      (node (ref "C46") (pin "-") (pinfunction "-_-") (pintype "passive"))
      (node (ref "C47") (pin "2") (pinfunction "2_2") (pintype "passive"))
      (node (ref "C48") (pin "2") (pinfunction "2_2") (pintype "passive"))
      (node (ref "C49") (pin "2") (pinfunction "2_2") (pintype "passive"))
      (node (ref "C5") (pin "1") (pinfunction "1_1") (pintype "passive"))
      (node (ref "C50") (pin "2") (pinfunction "2_2") (pintype "passive"))
      (node (ref "C51") (pin "2") (pinfunction "2_2") (pintype "passive"))
      (node (ref "C52") (pin "2") (pinfunction "2_2") (pintype "passive"))
      (node (ref "C6") (pin "1") (pinfunction "1_1") (pintype "passive"))
      (node (ref "C7") (pin "1") (pinfunction "1_1") (pintype "passive"))
      (node (ref "C8") (pin "1") (pinfunction "1_1") (pintype "passive"))
      (node (ref "C9") (pin "2") (pinfunction "2_2") (pintype "passive"))
      (node (ref "D1") (pin "A") (pinfunction "A_A") (pintype "passive"))
      (node (ref "D2") (pin "A") (pinfunction "A_A") (pintype "passive"))
      (node (ref "FINN-12V") (pin "3") (pinfunction "-VIN_3") (pintype "bidirectional"))
      (node (ref "FINN-12V") (pin "4") (pinfunction "-VOUT_4") (pintype "bidirectional"))
      (node (ref "LED1") (pin "C") (pinfunction "C_C") (pintype "passive"))
      (node (ref "LED10") (pin "C") (pinfunction "C_C") (pintype "passive"))
      (node (ref "LED11") (pin "C") (pinfunction "C_C") (pintype "passive"))
      (node (ref "LED12") (pin "C") (pinfunction "C_C") (pintype "passive"))
      (node (ref "LED2") (pin "C") (pinfunction "C_C") (pintype "passive"))
      (node (ref "LED3") (pin "C") (pinfunction "C_C") (pintype "passive"))
      (node (ref "LED6") (pin "C") (pinfunction "C_C") (pintype "passive"))
      (node (ref "LED7") (pin "C") (pinfunction "C_C") (pintype "passive"))
      (node (ref "LED8") (pin "C") (pinfunction "C_C") (pintype "passive"))
      (node (ref "LED9") (pin "C") (pinfunction "C_C") (pintype "passive"))
      (node (ref "M1-") (pin "P$1") (pinfunction "P$1_P$1") (pintype "bidirectional"))
      (node (ref "M2-") (pin "P$1") (pinfunction "P$1_P$1") (pintype "bidirectional"))
      (node (ref "M3-") (pin "P$1") (pinfunction "P$1_P$1") (pintype "bidirectional"))
      (node (ref "M4-") (pin "P$1") (pinfunction "P$1_P$1") (pintype "bidirectional"))
      (node (ref "M5-") (pin "P$1") (pinfunction "P$1_P$1") (pintype "bidirectional"))
      (node (ref "M6-") (pin "P$1") (pinfunction "P$1_P$1") (pintype "bidirectional"))
      (node (ref "POE-12V") (pin "3") (pinfunction "-VIN_3") (pintype "bidirectional"))
      (node (ref "POE-12V") (pin "4") (pinfunction "-VOUT_4") (pintype "bidirectional"))
      (node (ref "Q12") (pin "2") (pinfunction "S_2") (pintype "passive"))
      (node (ref "Q2") (pin "2") (pinfunction "S_2") (pintype "passive"))
      (node (ref "R13") (pin "2") (pinfunction "2_2") (pintype "passive"))
      (node (ref "R4") (pin "1") (pinfunction "1_1") (pintype "passive"))
      (node (ref "REY-5V") (pin "P$2") (pinfunction "-VIN_P$2") (pintype "bidirectional"))
      (node (ref "REY-5V") (pin "P$5") (pinfunction "-VOUT_P$5") (pintype "bidirectional"))
      (node (ref "REY-5V") (pin "P$8") (pinfunction "-SENSE_P$8") (pintype "bidirectional"))
      (node (ref "U$1") (pin "1") (pinfunction "GND_1") (pintype "bidirectional"))
      (node (ref "U$10") (pin "1") (pinfunction "GND_1") (pintype "bidirectional"))
      (node (ref "U$11") (pin "1") (pinfunction "GND_1") (pintype "bidirectional"))
      (node (ref "U$12") (pin "GND") (pinfunction "GND_GND") (pintype "bidirectional"))
      (node (ref "U$13") (pin "1") (pinfunction "GND_1") (pintype "bidirectional"))
      (node (ref "U$14") (pin "5") (pinfunction "GND_5") (pintype "bidirectional"))
      (node (ref "U$15") (pin "5") (pinfunction "GND_5") (pintype "bidirectional"))
      (node (ref "U$16") (pin "5") (pinfunction "GND_5") (pintype "bidirectional"))
      (node (ref "U$17") (pin "5") (pinfunction "GND_5") (pintype "bidirectional"))
      (node (ref "U$18") (pin "5") (pinfunction "GND_5") (pintype "bidirectional"))
      (node (ref "U$19") (pin "5") (pinfunction "GND_5") (pintype "bidirectional"))
      (node (ref "U$2") (pin "5") (pinfunction "GND_5") (pintype "bidirectional"))
      (node (ref "U$20") (pin "5") (pinfunction "GND_5") (pintype "bidirectional"))
      (node (ref "U$21") (pin "5") (pinfunction "GND_5") (pintype "bidirectional"))
      (node (ref "U$23") (pin "7") (pinfunction "7_7") (pintype "bidirectional"))
      (node (ref "U$23") (pin "8") (pinfunction "8_8") (pintype "bidirectional"))
      (node (ref "U$24") (pin "GND") (pinfunction "GND_GND") (pintype "bidirectional"))
      (node (ref "U$3") (pin "5") (pinfunction "GND_5") (pintype "bidirectional"))
      (node (ref "U$4") (pin "GND_1") (pinfunction "GND_GND_1") (pintype "bidirectional"))
      (node (ref "U$4") (pin "GND_2") (pinfunction "GND_GND_2") (pintype "bidirectional"))
      (node (ref "U$4") (pin "GND_3") (pinfunction "GND_GND_3") (pintype "bidirectional"))
      (node (ref "U$4") (pin "GND_4") (pinfunction "GND_GND_4") (pintype "bidirectional"))
      (node (ref "U$45") (pin "GND") (pinfunction "P$1_GND") (pintype "bidirectional"))
      (node (ref "U$46") (pin "GND") (pinfunction "P$1_GND") (pintype "bidirectional"))
      (node (ref "U$5") (pin "7") (pinfunction "7_7") (pintype "bidirectional"))
      (node (ref "U$5") (pin "8") (pinfunction "8_8") (pintype "bidirectional"))
      (node (ref "U$6") (pin "1") (pinfunction "GND_1") (pintype "bidirectional"))
      (node (ref "U$7") (pin "1") (pinfunction "GND_1") (pintype "bidirectional"))
      (node (ref "U$8") (pin "1") (pinfunction "GND_1") (pintype "bidirectional"))
      (node (ref "U$9") (pin "1") (pinfunction "GND_1") (pintype "bidirectional"))
    )
    (net (code "17") (name "M1-IMEAS") (class "Default")
      (node (ref "U$14") (pin "7") (pinfunction "VIOUT_7") (pintype "bidirectional"))
      (node (ref "U$4") (pin "PK3") (pinfunction "PK3_PK3") (pintype "bidirectional"))
    )
    (net (code "18") (name "M1-SIG") (class "Default")
      (node (ref "U$4") (pin "PP5") (pinfunction "PP5_PP5") (pintype "bidirectional"))
      (node (ref "U$6") (pin "4") (pinfunction "IN_4") (pintype "bidirectional"))
    )
    (net (code "19") (name "M2-IMEAS") (class "Default")
      (node (ref "U$15") (pin "7") (pinfunction "VIOUT_7") (pintype "bidirectional"))
      (node (ref "U$4") (pin "PK2") (pinfunction "PK2_PK2") (pintype "bidirectional"))
    )
    (net (code "20") (name "M2-SIG") (class "Default")
      (node (ref "U$4") (pin "PA7") (pinfunction "PA7_PA7") (pintype "bidirectional"))
      (node (ref "U$7") (pin "4") (pinfunction "IN_4") (pintype "bidirectional"))
    )
    (net (code "21") (name "M3-IMEAS") (class "Default")
      (node (ref "U$19") (pin "7") (pinfunction "VIOUT_7") (pintype "bidirectional"))
      (node (ref "U$4") (pin "PK1") (pinfunction "PK1_PK1") (pintype "bidirectional"))
    )
    (net (code "22") (name "M3-SIG") (class "Default")
      (node (ref "U$4") (pin "PH0") (pinfunction "PH0_PH0") (pintype "bidirectional"))
      (node (ref "U$8") (pin "4") (pinfunction "IN_4") (pintype "bidirectional"))
    )
    (net (code "23") (name "M4-IMEAS") (class "Default")
      (node (ref "U$18") (pin "7") (pinfunction "VIOUT_7") (pintype "bidirectional"))
      (node (ref "U$4") (pin "PD4") (pinfunction "PD4_PD4") (pintype "bidirectional"))
    )
    (net (code "24") (name "M4-SIG") (class "Default")
      (node (ref "U$4") (pin "PH1") (pinfunction "PH1_PH1") (pintype "bidirectional"))
      (node (ref "U$9") (pin "4") (pinfunction "IN_4") (pintype "bidirectional"))
    )
    (net (code "25") (name "M5-IMEAS") (class "Default")
      (node (ref "U$17") (pin "7") (pinfunction "VIOUT_7") (pintype "bidirectional"))
      (node (ref "U$4") (pin "PK0") (pinfunction "PK0_PK0") (pintype "bidirectional"))
    )
    (net (code "26") (name "M5-SIG") (class "Default")
      (node (ref "U$10") (pin "4") (pinfunction "IN_4") (pintype "bidirectional"))
      (node (ref "U$4") (pin "PP3") (pinfunction "PP3_PP3") (pintype "bidirectional"))
    )
    (net (code "27") (name "M6-IMEAS") (class "Default")
      (node (ref "U$16") (pin "7") (pinfunction "VIOUT_7") (pintype "bidirectional"))
      (node (ref "U$4") (pin "PB5") (pinfunction "PB5_PB5") (pintype "bidirectional"))
    )
    (net (code "28") (name "M6-SIG") (class "Default")
      (node (ref "U$11") (pin "4") (pinfunction "IN_4") (pintype "bidirectional"))
      (node (ref "U$4") (pin "PK6") (pinfunction "PK6_PK6") (pintype "bidirectional"))
    )
    (net (code "29") (name "Net-(FINN-12V-+VOUT)") (class "Default")
      (node (ref "C19") (pin "1") (pinfunction "1_1") (pintype "passive"))
      (node (ref "C20") (pin "1") (pinfunction "1_1") (pintype "passive"))
      (node (ref "C45") (pin "+") (pinfunction "+_+") (pintype "passive"))
      (node (ref "C46") (pin "+") (pinfunction "+_+") (pintype "passive"))
      (node (ref "FINN-12V") (pin "8") (pinfunction "+VOUT_8") (pintype "bidirectional"))
      (node (ref "POE-12V") (pin "8") (pinfunction "+VOUT_8") (pintype "bidirectional"))
      (node (ref "U$21") (pin "1") (pinfunction "IP+_1") (pintype "bidirectional"))
    )
    (net (code "30") (name "Net-(FINN-12V-REMOTE)") (class "Default")
      (node (ref "FINN-12V") (pin "2") (pinfunction "REMOTE_2") (pintype "bidirectional"))
      (node (ref "POE-12V") (pin "2") (pinfunction "REMOTE_2") (pintype "bidirectional"))
      (node (ref "Q12") (pin "3") (pinfunction "D_3") (pintype "passive"))
    )
    (net (code "31") (name "Net-(LED1-PadA)") (class "Default")
      (node (ref "LED1") (pin "A") (pinfunction "A_A") (pintype "passive"))
      (node (ref "R9") (pin "2") (pinfunction "2_2") (pintype "passive"))
    )
    (net (code "32") (name "Net-(LED2-PadA)") (class "Default")
      (node (ref "LED2") (pin "A") (pinfunction "A_A") (pintype "passive"))
      (node (ref "R10") (pin "2") (pinfunction "2_2") (pintype "passive"))
    )
    (net (code "33") (name "Net-(LED3-PadA)") (class "Default")
      (node (ref "LED3") (pin "A") (pinfunction "A_A") (pintype "passive"))
      (node (ref "R8") (pin "2") (pinfunction "2_2") (pintype "passive"))
    )
    (net (code "34") (name "Net-(LED5-PadC)") (class "Default")
      (node (ref "LED5") (pin "C") (pinfunction "C_C") (pintype "passive"))
      (node (ref "R13") (pin "1") (pinfunction "1_1") (pintype "passive"))
    )
    (net (code "35") (name "Net-(LED6-PadA)") (class "Default")
      (node (ref "LED6") (pin "A") (pinfunction "A_A") (pintype "passive"))
      (node (ref "R16") (pin "2") (pinfunction "2_2") (pintype "passive"))
    )
    (net (code "36") (name "Net-(LED7-PadA)") (class "Default")
      (node (ref "LED7") (pin "A") (pinfunction "A_A") (pintype "passive"))
      (node (ref "R18") (pin "2") (pinfunction "2_2") (pintype "passive"))
    )
    (net (code "37") (name "Net-(LED8-PadA)") (class "Default")
      (node (ref "LED8") (pin "A") (pinfunction "A_A") (pintype "passive"))
      (node (ref "R20") (pin "2") (pinfunction "2_2") (pintype "passive"))
    )
    (net (code "38") (name "Net-(LED9-PadA)") (class "Default")
      (node (ref "LED9") (pin "A") (pinfunction "A_A") (pintype "passive"))
      (node (ref "R22") (pin "2") (pinfunction "2_2") (pintype "passive"))
    )
    (net (code "39") (name "Net-(LED10-PadA)") (class "Default")
      (node (ref "LED10") (pin "A") (pinfunction "A_A") (pintype "passive"))
      (node (ref "R24") (pin "2") (pinfunction "2_2") (pintype "passive"))
    )
    (net (code "40") (name "Net-(LED11-PadA)") (class "Default")
      (node (ref "LED11") (pin "A") (pinfunction "A_A") (pintype "passive"))
      (node (ref "R5") (pin "2") (pinfunction "2_2") (pintype "passive"))
    )
    (net (code "41") (name "Net-(LED12-PadA)") (class "Default")
      (node (ref "LED12") (pin "A") (pinfunction "A_A") (pintype "passive"))
      (node (ref "R28") (pin "2") (pinfunction "2_2") (pintype "passive"))
    )
    (net (code "42") (name "Net-(Q1-D)") (class "Default")
      (node (ref "C7") (pin "2") (pinfunction "2_2") (pintype "passive"))
      (node (ref "Q1") (pin "TAB") (pinfunction "D_TAB") (pintype "bidirectional"))
      (node (ref "U$1") (pin "6") (pinfunction "SENSE_6") (pintype "bidirectional"))
      (node (ref "U$1") (pin "8") (pinfunction "V+_8") (pintype "bidirectional"))
      (node (ref "U$2") (pin "4") (pinfunction "IP-_4") (pintype "bidirectional"))
    )
    (net (code "43") (name "Net-(Q1-G)") (class "Default")
      (node (ref "Q1") (pin "1") (pinfunction "G_1") (pintype "bidirectional"))
      (node (ref "U$1") (pin "5") (pinfunction "GATE_5") (pintype "bidirectional"))
    )
    (net (code "44") (name "Net-(Q1-S)") (class "Default")
      (node (ref "AUX2+") (pin "P$1") (pinfunction "P$1_P$1") (pintype "bidirectional"))
      (node (ref "Q1") (pin "2") (pinfunction "S_2") (pintype "bidirectional"))
      (node (ref "R5") (pin "1") (pinfunction "1_1") (pintype "passive"))
    )
    (net (code "45") (name "Net-(Q2-D)") (class "Default")
      (node (ref "Q2") (pin "3") (pinfunction "D_3") (pintype "passive"))
      (node (ref "REY-5V") (pin "P$1") (pinfunction "ON/OFF_P$1") (pintype "bidirectional"))
    )
    (net (code "46") (name "Net-(Q2-G)") (class "Default")
      (node (ref "Q2") (pin "1") (pinfunction "G_1") (pintype "passive"))
      (node (ref "R11") (pin "1") (pinfunction "1_1") (pintype "passive"))
    )
    (net (code "47") (name "Net-(Q6-D)") (class "Default")
      (node (ref "C16") (pin "2") (pinfunction "2_2") (pintype "passive"))
      (node (ref "Q6") (pin "TAB") (pinfunction "D_TAB") (pintype "bidirectional"))
      (node (ref "U$14") (pin "4") (pinfunction "IP-_4") (pintype "bidirectional"))
      (node (ref "U$6") (pin "6") (pinfunction "SENSE_6") (pintype "bidirectional"))
      (node (ref "U$6") (pin "8") (pinfunction "V+_8") (pintype "bidirectional"))
    )
    (net (code "48") (name "Net-(Q6-G)") (class "Default")
      (node (ref "Q6") (pin "1") (pinfunction "G_1") (pintype "bidirectional"))
      (node (ref "U$6") (pin "5") (pinfunction "GATE_5") (pintype "bidirectional"))
    )
    (net (code "49") (name "Net-(Q6-S)") (class "Default")
      (node (ref "M1+") (pin "P$1") (pinfunction "P$1_P$1") (pintype "bidirectional"))
      (node (ref "Q6") (pin "2") (pinfunction "S_2") (pintype "bidirectional"))
      (node (ref "R9") (pin "1") (pinfunction "1_1") (pintype "passive"))
    )
    (net (code "50") (name "Net-(Q7-D)") (class "Default")
      (node (ref "C24") (pin "2") (pinfunction "2_2") (pintype "passive"))
      (node (ref "Q7") (pin "TAB") (pinfunction "D_TAB") (pintype "bidirectional"))
      (node (ref "U$15") (pin "4") (pinfunction "IP-_4") (pintype "bidirectional"))
      (node (ref "U$7") (pin "6") (pinfunction "SENSE_6") (pintype "bidirectional"))
      (node (ref "U$7") (pin "8") (pinfunction "V+_8") (pintype "bidirectional"))
    )
    (net (code "51") (name "Net-(Q7-G)") (class "Default")
      (node (ref "Q7") (pin "1") (pinfunction "G_1") (pintype "bidirectional"))
      (node (ref "U$7") (pin "5") (pinfunction "GATE_5") (pintype "bidirectional"))
    )
    (net (code "52") (name "Net-(Q7-S)") (class "Default")
      (node (ref "M2+") (pin "P$1") (pinfunction "P$1_P$1") (pintype "bidirectional"))
      (node (ref "Q7") (pin "2") (pinfunction "S_2") (pintype "bidirectional"))
      (node (ref "R16") (pin "1") (pinfunction "1_1") (pintype "passive"))
    )
    (net (code "53") (name "Net-(Q9-D)") (class "Default")
      (node (ref "C26") (pin "2") (pinfunction "2_2") (pintype "passive"))
      (node (ref "Q9") (pin "TAB") (pinfunction "D_TAB") (pintype "bidirectional"))
      (node (ref "U$19") (pin "4") (pinfunction "IP-_4") (pintype "bidirectional"))
      (node (ref "U$8") (pin "6") (pinfunction "SENSE_6") (pintype "bidirectional"))
      (node (ref "U$8") (pin "8") (pinfunction "V+_8") (pintype "bidirectional"))
    )
    (net (code "54") (name "Net-(Q9-G)") (class "Default")
      (node (ref "Q9") (pin "1") (pinfunction "G_1") (pintype "bidirectional"))
      (node (ref "U$8") (pin "5") (pinfunction "GATE_5") (pintype "bidirectional"))
    )
    (net (code "55") (name "Net-(Q9-S)") (class "Default")
      (node (ref "M3+") (pin "P$1") (pinfunction "P$1_P$1") (pintype "bidirectional"))
      (node (ref "Q9") (pin "2") (pinfunction "S_2") (pintype "bidirectional"))
      (node (ref "R18") (pin "1") (pinfunction "1_1") (pintype "passive"))
    )
    (net (code "56") (name "Net-(Q11-D)") (class "Default")
      (node (ref "C28") (pin "2") (pinfunction "2_2") (pintype "passive"))
      (node (ref "Q11") (pin "TAB") (pinfunction "D_TAB") (pintype "bidirectional"))
      (node (ref "U$18") (pin "4") (pinfunction "IP-_4") (pintype "bidirectional"))
      (node (ref "U$9") (pin "6") (pinfunction "SENSE_6") (pintype "bidirectional"))
      (node (ref "U$9") (pin "8") (pinfunction "V+_8") (pintype "bidirectional"))
    )
    (net (code "57") (name "Net-(Q11-G)") (class "Default")
      (node (ref "Q11") (pin "1") (pinfunction "G_1") (pintype "bidirectional"))
      (node (ref "U$9") (pin "5") (pinfunction "GATE_5") (pintype "bidirectional"))
    )
    (net (code "58") (name "Net-(Q11-S)") (class "Default")
      (node (ref "M4+") (pin "P$1") (pinfunction "P$1_P$1") (pintype "bidirectional"))
      (node (ref "Q11") (pin "2") (pinfunction "S_2") (pintype "bidirectional"))
      (node (ref "R20") (pin "1") (pinfunction "1_1") (pintype "passive"))
    )
    (net (code "59") (name "Net-(Q12-G)") (class "Default")
      (node (ref "Q12") (pin "1") (pinfunction "G_1") (pintype "passive"))
      (node (ref "R15") (pin "1") (pinfunction "1_1") (pintype "passive"))
    )
    (net (code "60") (name "Net-(Q14-D)") (class "Default")
      (node (ref "C30") (pin "2") (pinfunction "2_2") (pintype "passive"))
      (node (ref "Q14") (pin "TAB") (pinfunction "D_TAB") (pintype "bidirectional"))
      (node (ref "U$10") (pin "6") (pinfunction "SENSE_6") (pintype "bidirectional"))
      (node (ref "U$10") (pin "8") (pinfunction "V+_8") (pintype "bidirectional"))
      (node (ref "U$17") (pin "4") (pinfunction "IP-_4") (pintype "bidirectional"))
    )
    (net (code "61") (name "Net-(Q14-G)") (class "Default")
      (node (ref "Q14") (pin "1") (pinfunction "G_1") (pintype "bidirectional"))
      (node (ref "U$10") (pin "5") (pinfunction "GATE_5") (pintype "bidirectional"))
    )
    (net (code "62") (name "Net-(Q14-S)") (class "Default")
      (node (ref "M5+") (pin "P$1") (pinfunction "P$1_P$1") (pintype "bidirectional"))
      (node (ref "Q14") (pin "2") (pinfunction "S_2") (pintype "bidirectional"))
      (node (ref "R22") (pin "1") (pinfunction "1_1") (pintype "passive"))
    )
    (net (code "63") (name "Net-(Q16-D)") (class "Default")
      (node (ref "C32") (pin "2") (pinfunction "2_2") (pintype "passive"))
      (node (ref "Q16") (pin "TAB") (pinfunction "D_TAB") (pintype "bidirectional"))
      (node (ref "U$11") (pin "6") (pinfunction "SENSE_6") (pintype "bidirectional"))
      (node (ref "U$11") (pin "8") (pinfunction "V+_8") (pintype "bidirectional"))
      (node (ref "U$16") (pin "4") (pinfunction "IP-_4") (pintype "bidirectional"))
    )
    (net (code "64") (name "Net-(Q16-G)") (class "Default")
      (node (ref "Q16") (pin "1") (pinfunction "G_1") (pintype "bidirectional"))
      (node (ref "U$11") (pin "5") (pinfunction "GATE_5") (pintype "bidirectional"))
    )
    (net (code "65") (name "Net-(Q16-S)") (class "Default")
      (node (ref "M6+") (pin "P$1") (pinfunction "P$1_P$1") (pintype "bidirectional"))
      (node (ref "Q16") (pin "2") (pinfunction "S_2") (pintype "bidirectional"))
      (node (ref "R24") (pin "1") (pinfunction "1_1") (pintype "passive"))
    )
    (net (code "66") (name "Net-(Q20-D)") (class "Default")
      (node (ref "C36") (pin "2") (pinfunction "2_2") (pintype "passive"))
      (node (ref "Q20") (pin "TAB") (pinfunction "D_TAB") (pintype "bidirectional"))
      (node (ref "U$13") (pin "6") (pinfunction "SENSE_6") (pintype "bidirectional"))
      (node (ref "U$13") (pin "8") (pinfunction "V+_8") (pintype "bidirectional"))
      (node (ref "U$20") (pin "4") (pinfunction "IP-_4") (pintype "bidirectional"))
    )
    (net (code "67") (name "Net-(Q20-G)") (class "Default")
      (node (ref "Q20") (pin "1") (pinfunction "G_1") (pintype "bidirectional"))
      (node (ref "U$13") (pin "5") (pinfunction "GATE_5") (pintype "bidirectional"))
    )
    (net (code "68") (name "Net-(Q20-S)") (class "Default")
      (node (ref "AUX1+") (pin "P$1") (pinfunction "P$1_P$1") (pintype "bidirectional"))
      (node (ref "Q20") (pin "2") (pinfunction "S_2") (pintype "bidirectional"))
      (node (ref "R28") (pin "1") (pinfunction "1_1") (pintype "passive"))
    )
    (net (code "69") (name "Net-(R1-Pad1)") (class "Default")
      (node (ref "R1") (pin "1") (pinfunction "1_1") (pintype "passive"))
      (node (ref "U$12") (pin "A") (pinfunction "A_A") (pintype "bidirectional"))
      (node (ref "U$5") (pin "1") (pinfunction "1_1") (pintype "bidirectional"))
    )
    (net (code "70") (name "Net-(R1-Pad2)") (class "Default")
      (node (ref "R1") (pin "2") (pinfunction "2_2") (pintype "passive"))
      (node (ref "U$12") (pin "B") (pinfunction "B_B") (pintype "bidirectional"))
      (node (ref "U$5") (pin "2") (pinfunction "2_2") (pintype "bidirectional"))
    )
    (net (code "71") (name "Net-(R2-Pad1)") (class "Default")
      (node (ref "R2") (pin "1") (pinfunction "1_1") (pintype "passive"))
      (node (ref "U$23") (pin "1") (pinfunction "1_1") (pintype "bidirectional"))
      (node (ref "U$24") (pin "A") (pinfunction "A_A") (pintype "bidirectional"))
    )
    (net (code "72") (name "Net-(R2-Pad2)") (class "Default")
      (node (ref "R2") (pin "2") (pinfunction "2_2") (pintype "passive"))
      (node (ref "U$23") (pin "2") (pinfunction "2_2") (pintype "bidirectional"))
      (node (ref "U$24") (pin "B") (pinfunction "B_B") (pintype "bidirectional"))
    )
    (net (code "73") (name "Net-(R6-Pad1)") (class "Default")
      (node (ref "R6") (pin "1") (pinfunction "1_1") (pintype "passive"))
      (node (ref "U$12") (pin "Z") (pinfunction "Z_Z") (pintype "bidirectional"))
      (node (ref "U$5") (pin "6") (pinfunction "6_6") (pintype "bidirectional"))
    )
    (net (code "74") (name "Net-(R6-Pad2)") (class "Default")
      (node (ref "R6") (pin "2") (pinfunction "2_2") (pintype "passive"))
      (node (ref "U$12") (pin "Y") (pinfunction "Y_Y") (pintype "bidirectional"))
      (node (ref "U$5") (pin "3") (pinfunction "3_3") (pintype "bidirectional"))
    )
    (net (code "75") (name "Net-(R7-Pad1)") (class "Default")
      (node (ref "R7") (pin "1") (pinfunction "1_1") (pintype "passive"))
      (node (ref "U$23") (pin "6") (pinfunction "6_6") (pintype "bidirectional"))
      (node (ref "U$24") (pin "Z") (pinfunction "Z_Z") (pintype "bidirectional"))
    )
    (net (code "76") (name "Net-(R7-Pad2)") (class "Default")
      (node (ref "R7") (pin "2") (pinfunction "2_2") (pintype "passive"))
      (node (ref "U$23") (pin "3") (pinfunction "3_3") (pintype "bidirectional"))
      (node (ref "U$24") (pin "Y") (pinfunction "Y_Y") (pintype "bidirectional"))
    )
    (net (code "77") (name "Net-(REY-5V-+SENSE)") (class "Default")
      (node (ref "C22") (pin "+") (pinfunction "+_+") (pintype "passive"))
      (node (ref "REY-5V") (pin "P$6") (pinfunction "+VOUT_P$6") (pintype "bidirectional"))
      (node (ref "REY-5V") (pin "P$7") (pinfunction "+SENSE_P$7") (pintype "bidirectional"))
      (node (ref "U$3") (pin "1") (pinfunction "IP+_1") (pintype "bidirectional"))
    )
    (net (code "78") (name "Net-(U$2-FILTER)") (class "Default")
      (node (ref "C9") (pin "1") (pinfunction "1_1") (pintype "passive"))
      (node (ref "U$2") (pin "6") (pinfunction "FILTER_6") (pintype "bidirectional"))
    )
    (net (code "79") (name "Net-(U$3-FILTER)") (class "Default")
      (node (ref "C12") (pin "1") (pinfunction "1_1") (pintype "passive"))
      (node (ref "U$3") (pin "6") (pinfunction "FILTER_6") (pintype "bidirectional"))
    )
    (net (code "80") (name "Net-(U$4-+3V3-Pad+3V3_1)") (class "Default")
      (node (ref "U$4") (pin "+3V3_1") (pinfunction "+3V3_+3V3_1") (pintype "bidirectional"))
      (node (ref "U$4") (pin "+3V3_2") (pinfunction "+3V3_+3V3_2") (pintype "bidirectional"))
    )
    (net (code "81") (name "Net-(U$4-RST-PadRST1)") (class "Default")
      (node (ref "U$4") (pin "RST1") (pinfunction "RST_RST1") (pintype "bidirectional"))
      (node (ref "U$4") (pin "RST_2") (pinfunction "RST_RST_2") (pintype "bidirectional"))
    )
    (net (code "82") (name "Net-(U$14-FILTER)") (class "Default")
      (node (ref "C37") (pin "1") (pinfunction "1_1") (pintype "passive"))
      (node (ref "U$14") (pin "6") (pinfunction "FILTER_6") (pintype "bidirectional"))
    )
    (net (code "83") (name "Net-(U$15-FILTER)") (class "Default")
      (node (ref "C38") (pin "1") (pinfunction "1_1") (pintype "passive"))
      (node (ref "U$15") (pin "6") (pinfunction "FILTER_6") (pintype "bidirectional"))
    )
    (net (code "84") (name "Net-(U$16-FILTER)") (class "Default")
      (node (ref "C27") (pin "1") (pinfunction "1_1") (pintype "passive"))
      (node (ref "U$16") (pin "6") (pinfunction "FILTER_6") (pintype "bidirectional"))
    )
    (net (code "85") (name "Net-(U$17-FILTER)") (class "Default")
      (node (ref "C31") (pin "1") (pinfunction "1_1") (pintype "passive"))
      (node (ref "U$17") (pin "6") (pinfunction "FILTER_6") (pintype "bidirectional"))
    )
    (net (code "86") (name "Net-(U$18-FILTER)") (class "Default")
      (node (ref "C35") (pin "1") (pinfunction "1_1") (pintype "passive"))
      (node (ref "U$18") (pin "6") (pinfunction "FILTER_6") (pintype "bidirectional"))
    )
    (net (code "87") (name "Net-(U$19-FILTER)") (class "Default")
      (node (ref "C40") (pin "1") (pinfunction "1_1") (pintype "passive"))
      (node (ref "U$19") (pin "6") (pinfunction "FILTER_6") (pintype "bidirectional"))
    )
    (net (code "88") (name "Net-(U$20-FILTER)") (class "Default")
      (node (ref "C42") (pin "1") (pinfunction "1_1") (pintype "passive"))
      (node (ref "U$20") (pin "6") (pinfunction "FILTER_6") (pintype "bidirectional"))
    )
    (net (code "89") (name "Net-(U$21-FILTER)") (class "Default")
      (node (ref "C43") (pin "1") (pinfunction "1_1") (pintype "passive"))
      (node (ref "U$21") (pin "6") (pinfunction "FILTER_6") (pintype "bidirectional"))
    )
    (net (code "90") (name "PRIMARY-VMEAS") (class "Default")
      (node (ref "R3") (pin "1") (pinfunction "1_1") (pintype "passive"))
      (node (ref "R4") (pin "2") (pinfunction "2_2") (pintype "passive"))
      (node (ref "U$4") (pin "PD7") (pinfunction "PD7_PD7") (pintype "bidirectional"))
    )
    (net (code "91") (name "V_BATT") (class "Default")
      (node (ref "BATT-POS") (pin "P$1") (pinfunction "P$1_P$1") (pintype "bidirectional"))
      (node (ref "BB-8-5V") (pin "1") (pinfunction "VI_1") (pintype "bidirectional"))
      (node (ref "C1") (pin "+") (pinfunction "+_+") (pintype "passive"))
      (node (ref "C2") (pin "+") (pinfunction "+_+") (pintype "passive"))
      (node (ref "C3") (pin "+") (pinfunction "+_+") (pintype "passive"))
      (node (ref "C4") (pin "+") (pinfunction "+_+") (pintype "passive"))
      (node (ref "D1") (pin "C") (pinfunction "C_C") (pintype "passive"))
      (node (ref "D2") (pin "C") (pinfunction "C_C") (pintype "passive"))
      (node (ref "FINN-12V") (pin "1") (pinfunction "+VIN_1") (pintype "bidirectional"))
      (node (ref "POE-12V") (pin "1") (pinfunction "+VIN_1") (pintype "bidirectional"))
      (node (ref "R3") (pin "2") (pinfunction "2_2") (pintype "passive"))
      (node (ref "REY-5V") (pin "P$3") (pinfunction "+VIN_P$3") (pintype "bidirectional"))
      (node (ref "U$14") (pin "1") (pinfunction "IP+_1") (pintype "bidirectional"))
      (node (ref "U$15") (pin "1") (pinfunction "IP+_1") (pintype "bidirectional"))
      (node (ref "U$16") (pin "1") (pinfunction "IP+_1") (pintype "bidirectional"))
      (node (ref "U$17") (pin "1") (pinfunction "IP+_1") (pintype "bidirectional"))
      (node (ref "U$18") (pin "1") (pinfunction "IP+_1") (pintype "bidirectional"))
      (node (ref "U$19") (pin "1") (pinfunction "IP+_1") (pintype "bidirectional"))
      (node (ref "U$2") (pin "1") (pinfunction "IP+_1") (pintype "bidirectional"))
      (node (ref "U$20") (pin "1") (pinfunction "IP+_1") (pintype "bidirectional"))
    )
    (net (code "92") (name "unconnected-(REY-5V-TRIM-PadP$4)") (class "Default")
      (node (ref "REY-5V") (pin "P$4") (pinfunction "TRIM_P$4") (pintype "bidirectional"))
    )
    (net (code "93") (name "unconnected-(U$1-FAULT-Pad3)") (class "Default")
      (node (ref "U$1") (pin "3") (pinfunction "FAULT_3") (pintype "bidirectional"))
    )
    (net (code "94") (name "unconnected-(U$1-TIMER-Pad2)") (class "Default")
      (node (ref "U$1") (pin "2") (pinfunction "TIMER_2") (pintype "bidirectional"))
    )
    (net (code "95") (name "unconnected-(U$4-PadPA4)") (class "Default")
      (node (ref "U$4") (pin "PA4") (pinfunction "PA4_PA4") (pintype "bidirectional"))
    )
    (net (code "96") (name "unconnected-(U$4-PadPA5)") (class "Default")
      (node (ref "U$4") (pin "PA5") (pinfunction "PA5_PA5") (pintype "bidirectional"))
    )
    (net (code "97") (name "unconnected-(U$4-PadPA6)") (class "Default")
      (node (ref "U$4") (pin "PA6") (pinfunction "PA6_PA6") (pintype "bidirectional"))
    )
    (net (code "98") (name "unconnected-(U$4-PadPB2)") (class "Default")
      (node (ref "U$4") (pin "PB2") (pinfunction "PB2_PB2") (pintype "bidirectional"))
    )
    (net (code "99") (name "unconnected-(U$4-PadPB3)") (class "Default")
      (node (ref "U$4") (pin "PB3") (pinfunction "PB3_PB3") (pintype "bidirectional"))
    )
    (net (code "100") (name "unconnected-(U$4-PadPC6)") (class "Default")
      (node (ref "U$4") (pin "PC6") (pinfunction "PC6_PC6") (pintype "bidirectional"))
    )
    (net (code "101") (name "unconnected-(U$4-PadPC7)") (class "Default")
      (node (ref "U$4") (pin "PC7") (pinfunction "PC7_PC7") (pintype "bidirectional"))
    )
    (net (code "102") (name "unconnected-(U$4-PadPD3)") (class "Default")
      (node (ref "U$4") (pin "PD3") (pinfunction "PD3_PD3") (pintype "bidirectional"))
    )
    (net (code "103") (name "unconnected-(U$4-PadPD5)") (class "Default")
      (node (ref "U$4") (pin "PD5") (pinfunction "PD5_PD5") (pintype "bidirectional"))
    )
    (net (code "104") (name "unconnected-(U$4-PadPE0)") (class "Default")
      (node (ref "U$4") (pin "PE0") (pinfunction "PE0_PE0") (pintype "bidirectional"))
    )
    (net (code "105") (name "unconnected-(U$4-PadPE1)") (class "Default")
      (node (ref "U$4") (pin "PE1") (pinfunction "PE1_PE1") (pintype "bidirectional"))
    )
    (net (code "106") (name "unconnected-(U$4-PadPE2)") (class "Default")
      (node (ref "U$4") (pin "PE2") (pinfunction "PE2_PE2") (pintype "bidirectional"))
    )
    (net (code "107") (name "unconnected-(U$4-PadPE3)") (class "Default")
      (node (ref "U$4") (pin "PE3") (pinfunction "PE3_PE3") (pintype "bidirectional"))
    )
    (net (code "108") (name "unconnected-(U$4-PadPE4)") (class "Default")
      (node (ref "U$4") (pin "PE4") (pinfunction "PE4_PE4") (pintype "bidirectional"))
    )
    (net (code "109") (name "unconnected-(U$4-PadPE5)") (class "Default")
      (node (ref "U$4") (pin "PE5") (pinfunction "PE5_PE5") (pintype "bidirectional"))
    )
    (net (code "110") (name "unconnected-(U$4-PadPF1)") (class "Default")
      (node (ref "U$4") (pin "PF1") (pinfunction "PF1_PF1") (pintype "bidirectional"))
    )
    (net (code "111") (name "unconnected-(U$4-PadPF2)") (class "Default")
      (node (ref "U$4") (pin "PF2") (pinfunction "PF2_PF2") (pintype "bidirectional"))
    )
    (net (code "112") (name "unconnected-(U$4-PadPF3)") (class "Default")
      (node (ref "U$4") (pin "PF3") (pinfunction "PF3_PF3") (pintype "bidirectional"))
    )
    (net (code "113") (name "unconnected-(U$4-PadPG0)") (class "Default")
      (node (ref "U$4") (pin "PG0") (pinfunction "PG0_PG0") (pintype "bidirectional"))
    )
    (net (code "114") (name "unconnected-(U$4-PadPG1)") (class "Default")
      (node (ref "U$4") (pin "PG1") (pinfunction "PG1_PG1") (pintype "bidirectional"))
    )
    (net (code "115") (name "unconnected-(U$4-PadPH2)") (class "Default")
      (node (ref "U$4") (pin "PH2") (pinfunction "PH2_PH2") (pintype "bidirectional"))
    )
    (net (code "116") (name "unconnected-(U$4-PadPH3)") (class "Default")
      (node (ref "U$4") (pin "PH3") (pinfunction "PH3_PH3") (pintype "bidirectional"))
    )
    (net (code "117") (name "unconnected-(U$4-PadPK4)") (class "Default")
      (node (ref "U$4") (pin "PK4") (pinfunction "PK4_PK4") (pintype "bidirectional"))
    )
    (net (code "118") (name "unconnected-(U$4-PadPK5)") (class "Default")
      (node (ref "U$4") (pin "PK5") (pinfunction "PK5_PK5") (pintype "bidirectional"))
    )
    (net (code "119") (name "unconnected-(U$4-PadPL0)") (class "Default")
      (node (ref "U$4") (pin "PL0") (pinfunction "PL0_PL0") (pintype "bidirectional"))
    )
    (net (code "120") (name "unconnected-(U$4-PadPL1)") (class "Default")
      (node (ref "U$4") (pin "PL1") (pinfunction "PL1_PL1") (pintype "bidirectional"))
    )
    (net (code "121") (name "unconnected-(U$4-PadPL2)") (class "Default")
      (node (ref "U$4") (pin "PL2") (pinfunction "PL2_PL2") (pintype "bidirectional"))
    )
    (net (code "122") (name "unconnected-(U$4-PadPL3)") (class "Default")
      (node (ref "U$4") (pin "PL3") (pinfunction "PL3_PL3") (pintype "bidirectional"))
    )
    (net (code "123") (name "unconnected-(U$4-PadPL4)") (class "Default")
      (node (ref "U$4") (pin "PL4") (pinfunction "PL4_PL4") (pintype "bidirectional"))
    )
    (net (code "124") (name "unconnected-(U$4-PadPL5)") (class "Default")
      (node (ref "U$4") (pin "PL5") (pinfunction "PL5_PL5") (pintype "bidirectional"))
    )
    (net (code "125") (name "unconnected-(U$4-PadPM0)") (class "Default")
      (node (ref "U$4") (pin "PM0") (pinfunction "PM0_PM0") (pintype "bidirectional"))
    )
    (net (code "126") (name "unconnected-(U$4-PadPM1)") (class "Default")
      (node (ref "U$4") (pin "PM1") (pinfunction "PM1_PM1") (pintype "bidirectional"))
    )
    (net (code "127") (name "unconnected-(U$4-PadPM2)") (class "Default")
      (node (ref "U$4") (pin "PM2") (pinfunction "PM2_PM2") (pintype "bidirectional"))
    )
    (net (code "128") (name "unconnected-(U$4-PadPM3)") (class "Default")
      (node (ref "U$4") (pin "PM3") (pinfunction "PM3_PM3") (pintype "bidirectional"))
    )
    (net (code "129") (name "unconnected-(U$4-PadPM4)") (class "Default")
      (node (ref "U$4") (pin "PM4") (pinfunction "PM4_PM4") (pintype "bidirectional"))
    )
    (net (code "130") (name "unconnected-(U$4-PadPM5)") (class "Default")
      (node (ref "U$4") (pin "PM5") (pinfunction "PM5_PM5") (pintype "bidirectional"))
    )
    (net (code "131") (name "unconnected-(U$4-PadPM6)") (class "Default")
      (node (ref "U$4") (pin "PM6") (pinfunction "PM6_PM6") (pintype "bidirectional"))
    )
    (net (code "132") (name "unconnected-(U$4-PadPM7)") (class "Default")
      (node (ref "U$4") (pin "PM7") (pinfunction "PM7_PM7") (pintype "bidirectional"))
    )
    (net (code "133") (name "unconnected-(U$4-PadPN2)") (class "Default")
      (node (ref "U$4") (pin "PN2") (pinfunction "PN2_PN2") (pintype "bidirectional"))
    )
    (net (code "134") (name "unconnected-(U$4-PadPN4)") (class "Default")
      (node (ref "U$4") (pin "PN4") (pinfunction "PN4_PN4") (pintype "bidirectional"))
    )
    (net (code "135") (name "unconnected-(U$4-PadPN5)") (class "Default")
      (node (ref "U$4") (pin "PN5") (pinfunction "PN5_PN5") (pintype "bidirectional"))
    )
    (net (code "136") (name "unconnected-(U$4-PadPP4)") (class "Default")
      (node (ref "U$4") (pin "PP4") (pinfunction "PP4_PP4") (pintype "bidirectional"))
    )
    (net (code "137") (name "unconnected-(U$4-PadPQ0)") (class "Default")
      (node (ref "U$4") (pin "PQ0") (pinfunction "PQ0_PQ0") (pintype "bidirectional"))
    )
    (net (code "138") (name "unconnected-(U$4-PadPQ2{slash}PA3)") (class "Default")
      (node (ref "U$4") (pin "PQ2/PA3") (pinfunction "PQ2/PA3_PQ2/PA3") (pintype "bidirectional"))
    )
    (net (code "139") (name "unconnected-(U$4-PadPQ3{slash}PA2)") (class "Default")
      (node (ref "U$4") (pin "PQ3/PA2") (pinfunction "PQ3/PA2_PQ3/PA2") (pintype "bidirectional"))
    )
    (net (code "140") (name "unconnected-(U$5-Pad4)") (class "Default")
      (node (ref "U$5") (pin "4") (pinfunction "4_4") (pintype "bidirectional"))
    )
    (net (code "141") (name "unconnected-(U$5-Pad5)") (class "Default")
      (node (ref "U$5") (pin "5") (pinfunction "5_5") (pintype "bidirectional"))
    )
    (net (code "142") (name "unconnected-(U$6-FAULT-Pad3)") (class "Default")
      (node (ref "U$6") (pin "3") (pinfunction "FAULT_3") (pintype "bidirectional"))
    )
    (net (code "143") (name "unconnected-(U$6-TIMER-Pad2)") (class "Default")
      (node (ref "U$6") (pin "2") (pinfunction "TIMER_2") (pintype "bidirectional"))
    )
    (net (code "144") (name "unconnected-(U$7-FAULT-Pad3)") (class "Default")
      (node (ref "U$7") (pin "3") (pinfunction "FAULT_3") (pintype "bidirectional"))
    )
    (net (code "145") (name "unconnected-(U$7-TIMER-Pad2)") (class "Default")
      (node (ref "U$7") (pin "2") (pinfunction "TIMER_2") (pintype "bidirectional"))
    )
    (net (code "146") (name "unconnected-(U$8-FAULT-Pad3)") (class "Default")
      (node (ref "U$8") (pin "3") (pinfunction "FAULT_3") (pintype "bidirectional"))
    )
    (net (code "147") (name "unconnected-(U$8-TIMER-Pad2)") (class "Default")
      (node (ref "U$8") (pin "2") (pinfunction "TIMER_2") (pintype "bidirectional"))
    )
    (net (code "148") (name "unconnected-(U$9-FAULT-Pad3)") (class "Default")
      (node (ref "U$9") (pin "3") (pinfunction "FAULT_3") (pintype "bidirectional"))
    )
    (net (code "149") (name "unconnected-(U$9-TIMER-Pad2)") (class "Default")
      (node (ref "U$9") (pin "2") (pinfunction "TIMER_2") (pintype "bidirectional"))
    )
    (net (code "150") (name "unconnected-(U$10-FAULT-Pad3)") (class "Default")
      (node (ref "U$10") (pin "3") (pinfunction "FAULT_3") (pintype "bidirectional"))
    )
    (net (code "151") (name "unconnected-(U$10-TIMER-Pad2)") (class "Default")
      (node (ref "U$10") (pin "2") (pinfunction "TIMER_2") (pintype "bidirectional"))
    )
    (net (code "152") (name "unconnected-(U$11-FAULT-Pad3)") (class "Default")
      (node (ref "U$11") (pin "3") (pinfunction "FAULT_3") (pintype "bidirectional"))
    )
    (net (code "153") (name "unconnected-(U$11-TIMER-Pad2)") (class "Default")
      (node (ref "U$11") (pin "2") (pinfunction "TIMER_2") (pintype "bidirectional"))
    )
    (net (code "154") (name "unconnected-(U$13-FAULT-Pad3)") (class "Default")
      (node (ref "U$13") (pin "3") (pinfunction "FAULT_3") (pintype "bidirectional"))
    )
    (net (code "155") (name "unconnected-(U$13-TIMER-Pad2)") (class "Default")
      (node (ref "U$13") (pin "2") (pinfunction "TIMER_2") (pintype "bidirectional"))
    )
    (net (code "156") (name "unconnected-(U$23-Pad4)") (class "Default")
      (node (ref "U$23") (pin "4") (pinfunction "4_4") (pintype "bidirectional"))
    )
    (net (code "157") (name "unconnected-(U$23-Pad5)") (class "Default")
      (node (ref "U$23") (pin "5") (pinfunction "5_5") (pintype "bidirectional"))
    )
  )
)
